# plaits_v50.net
KiCad netlist of a schematic drawn in EAGLE
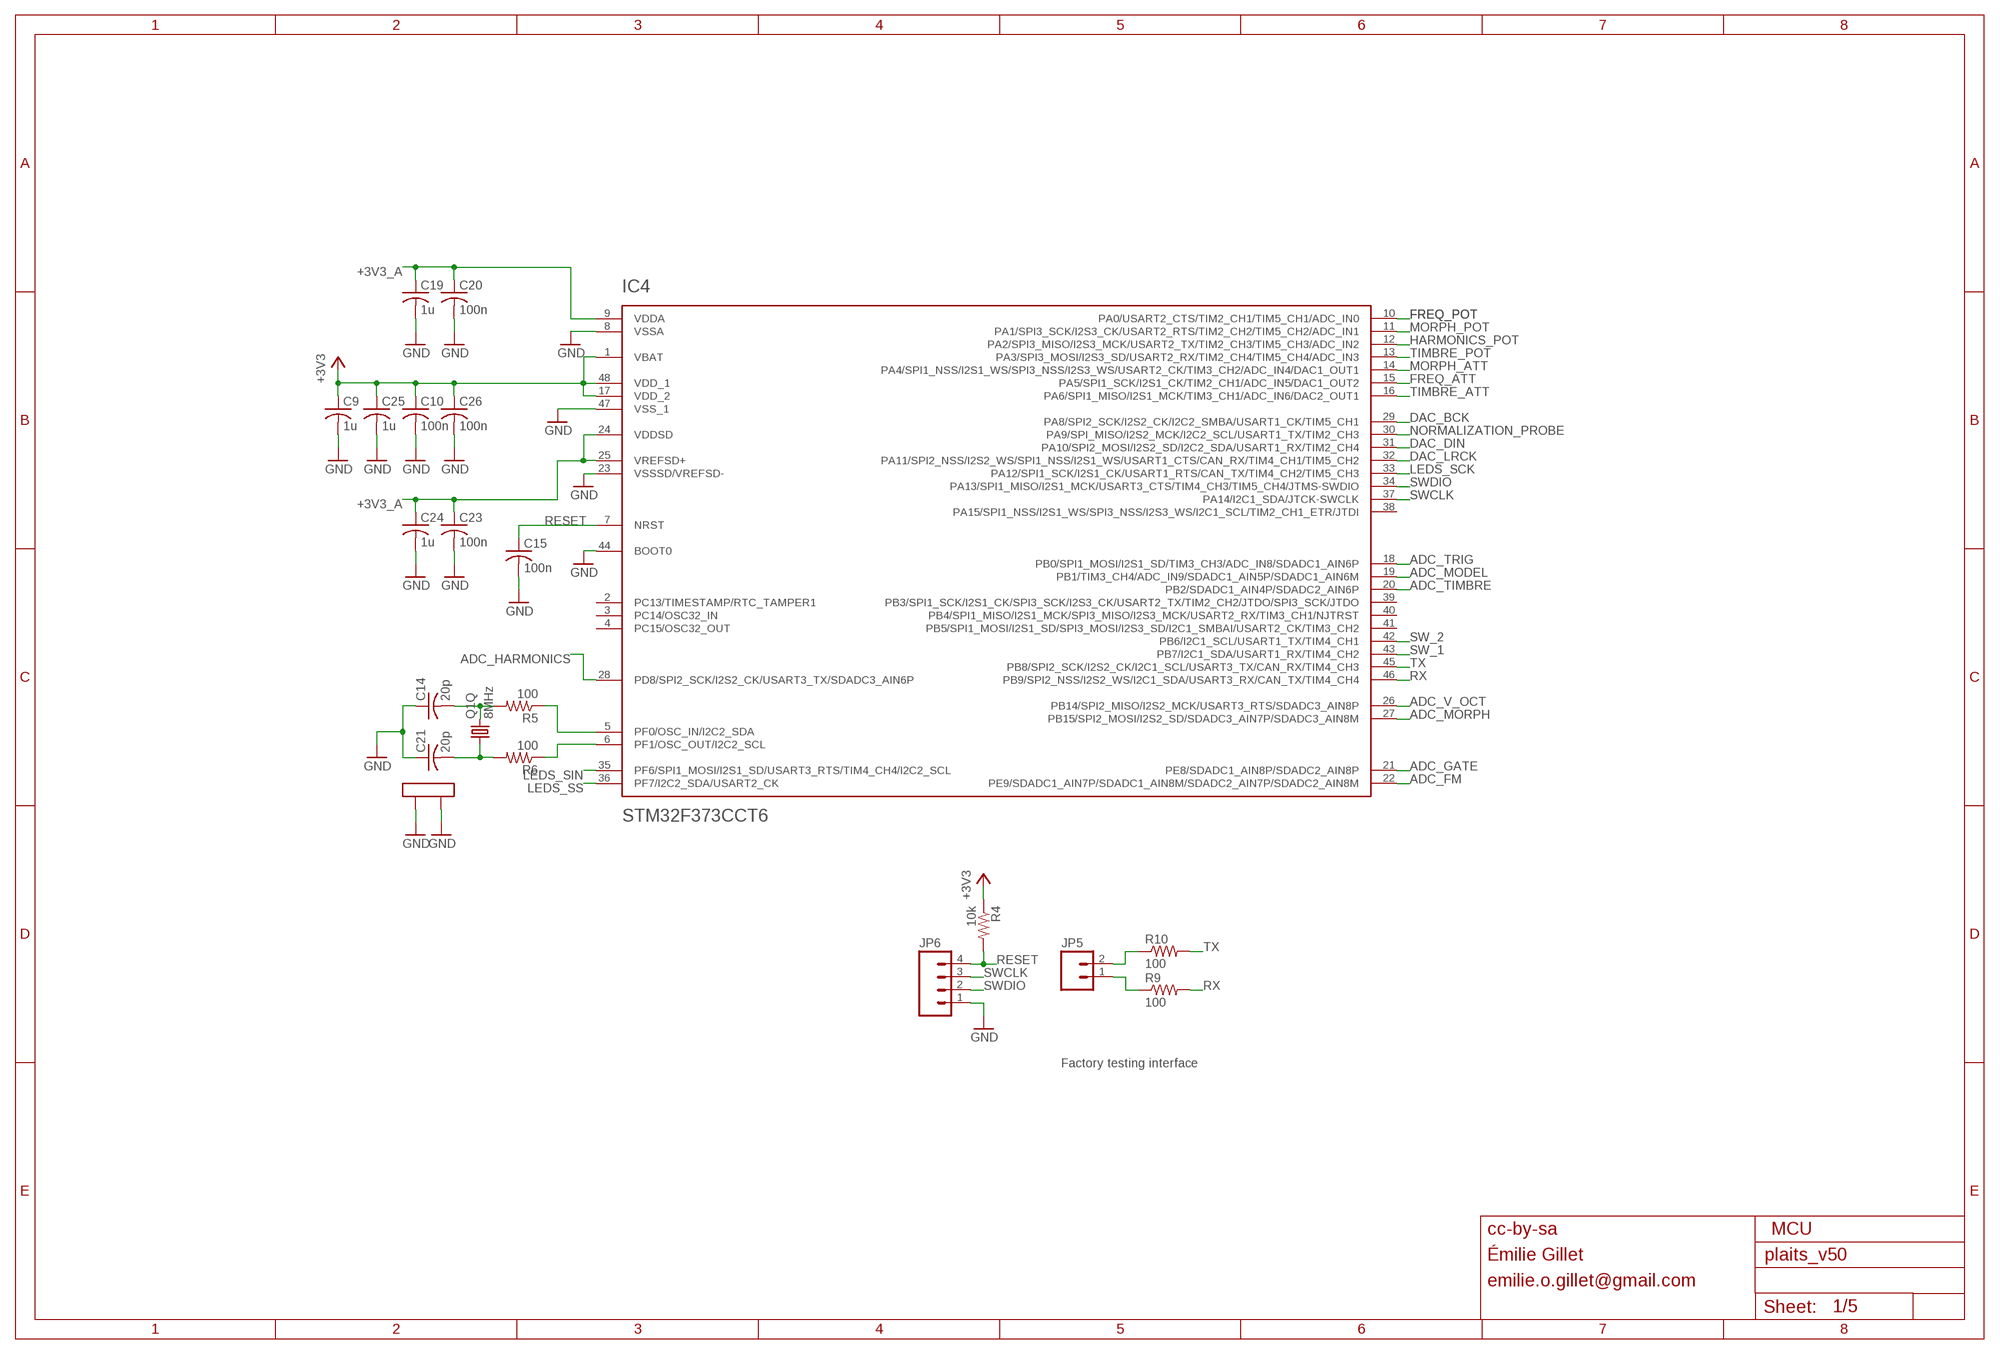
[diagram p0: schematic, sheet 1]
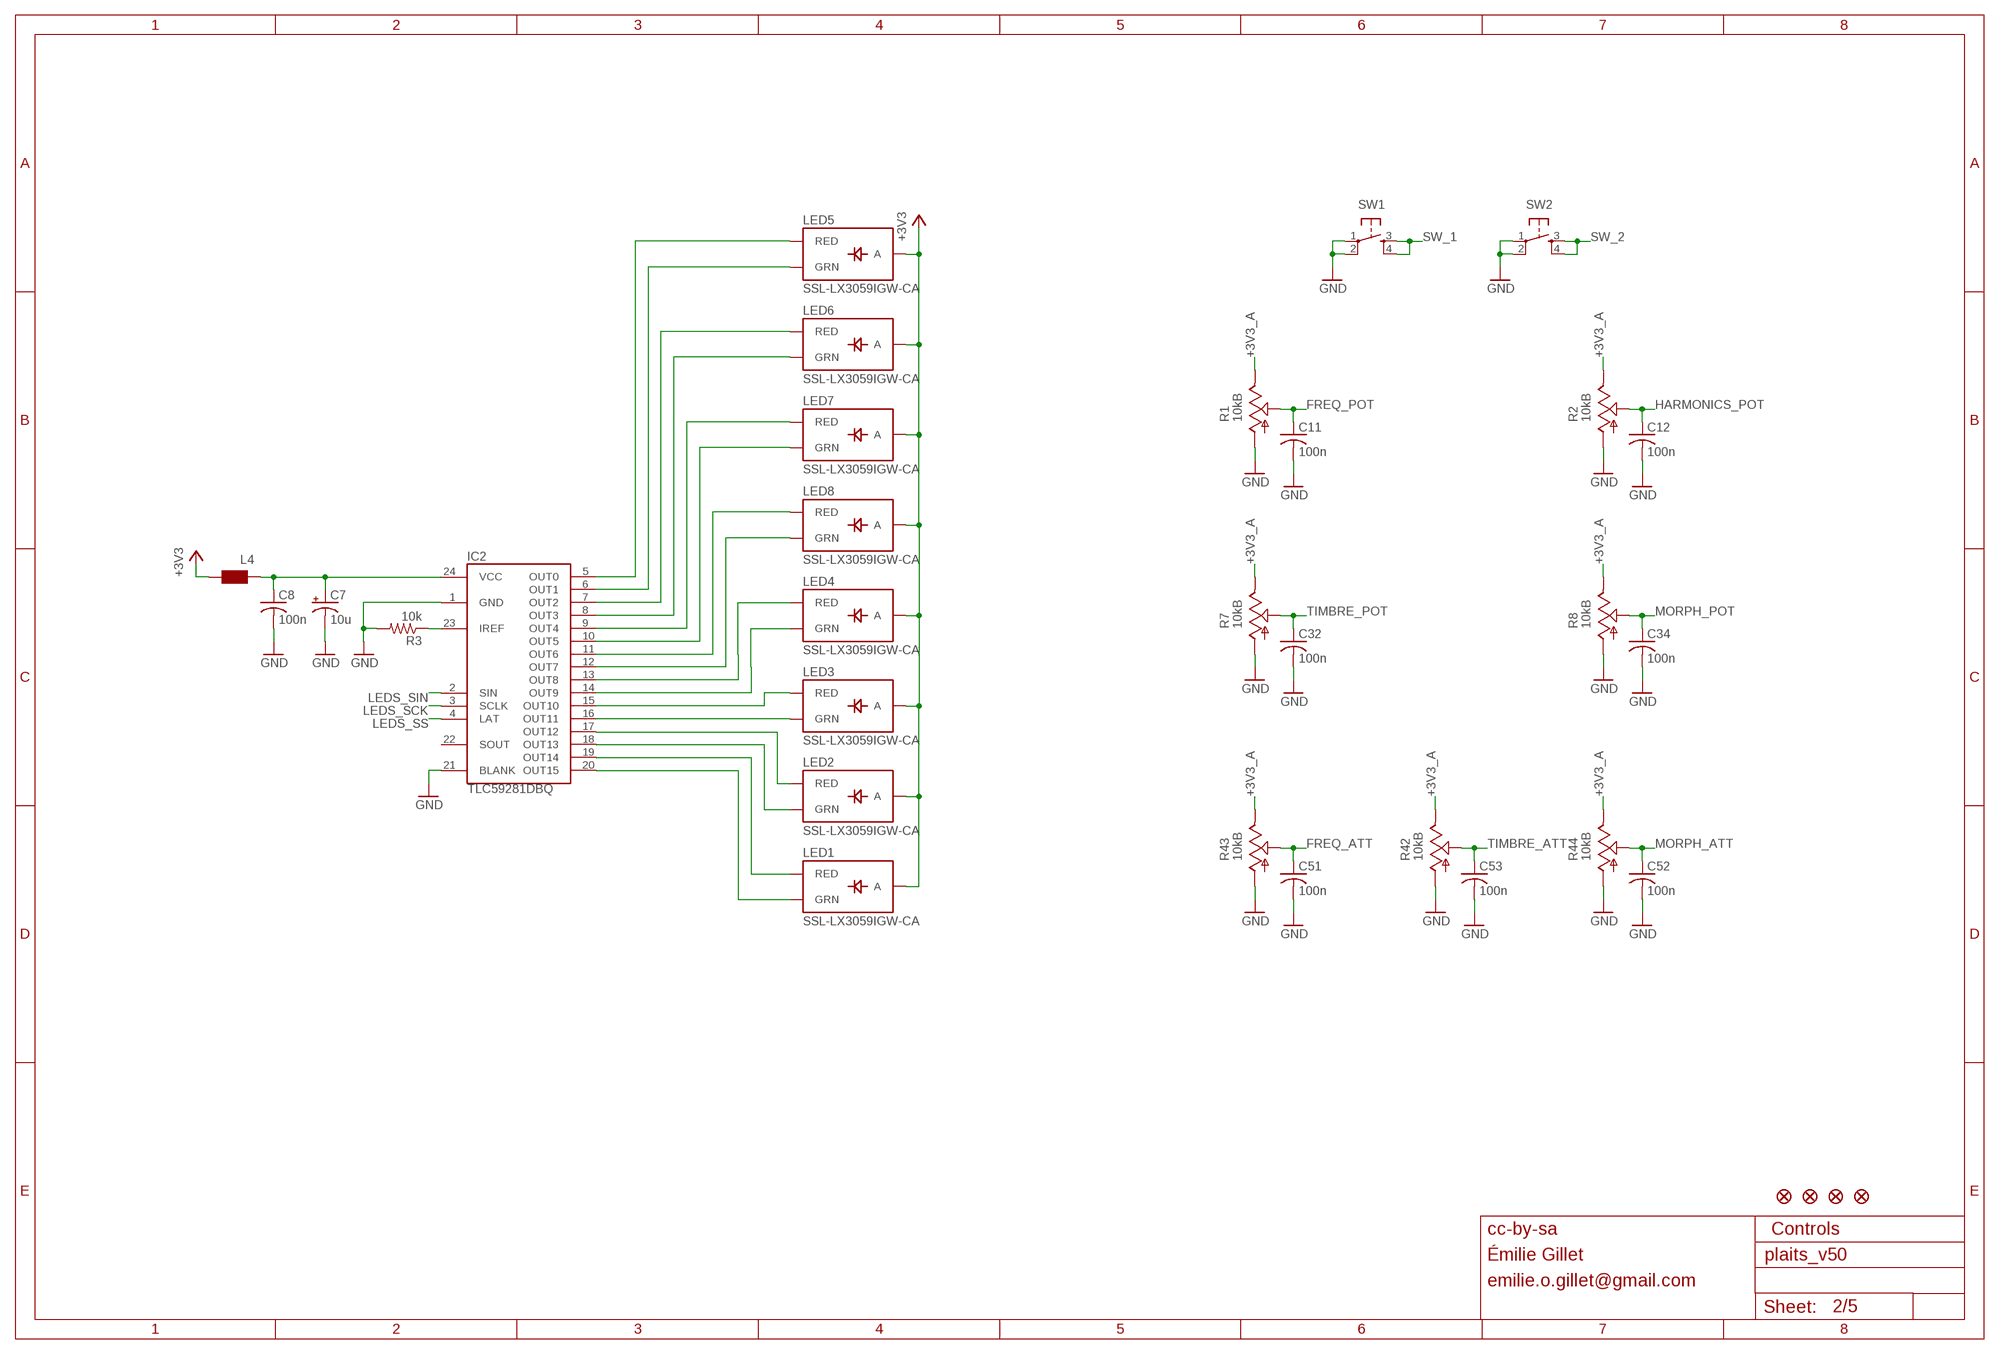
[diagram p1: schematic, sheet 2]
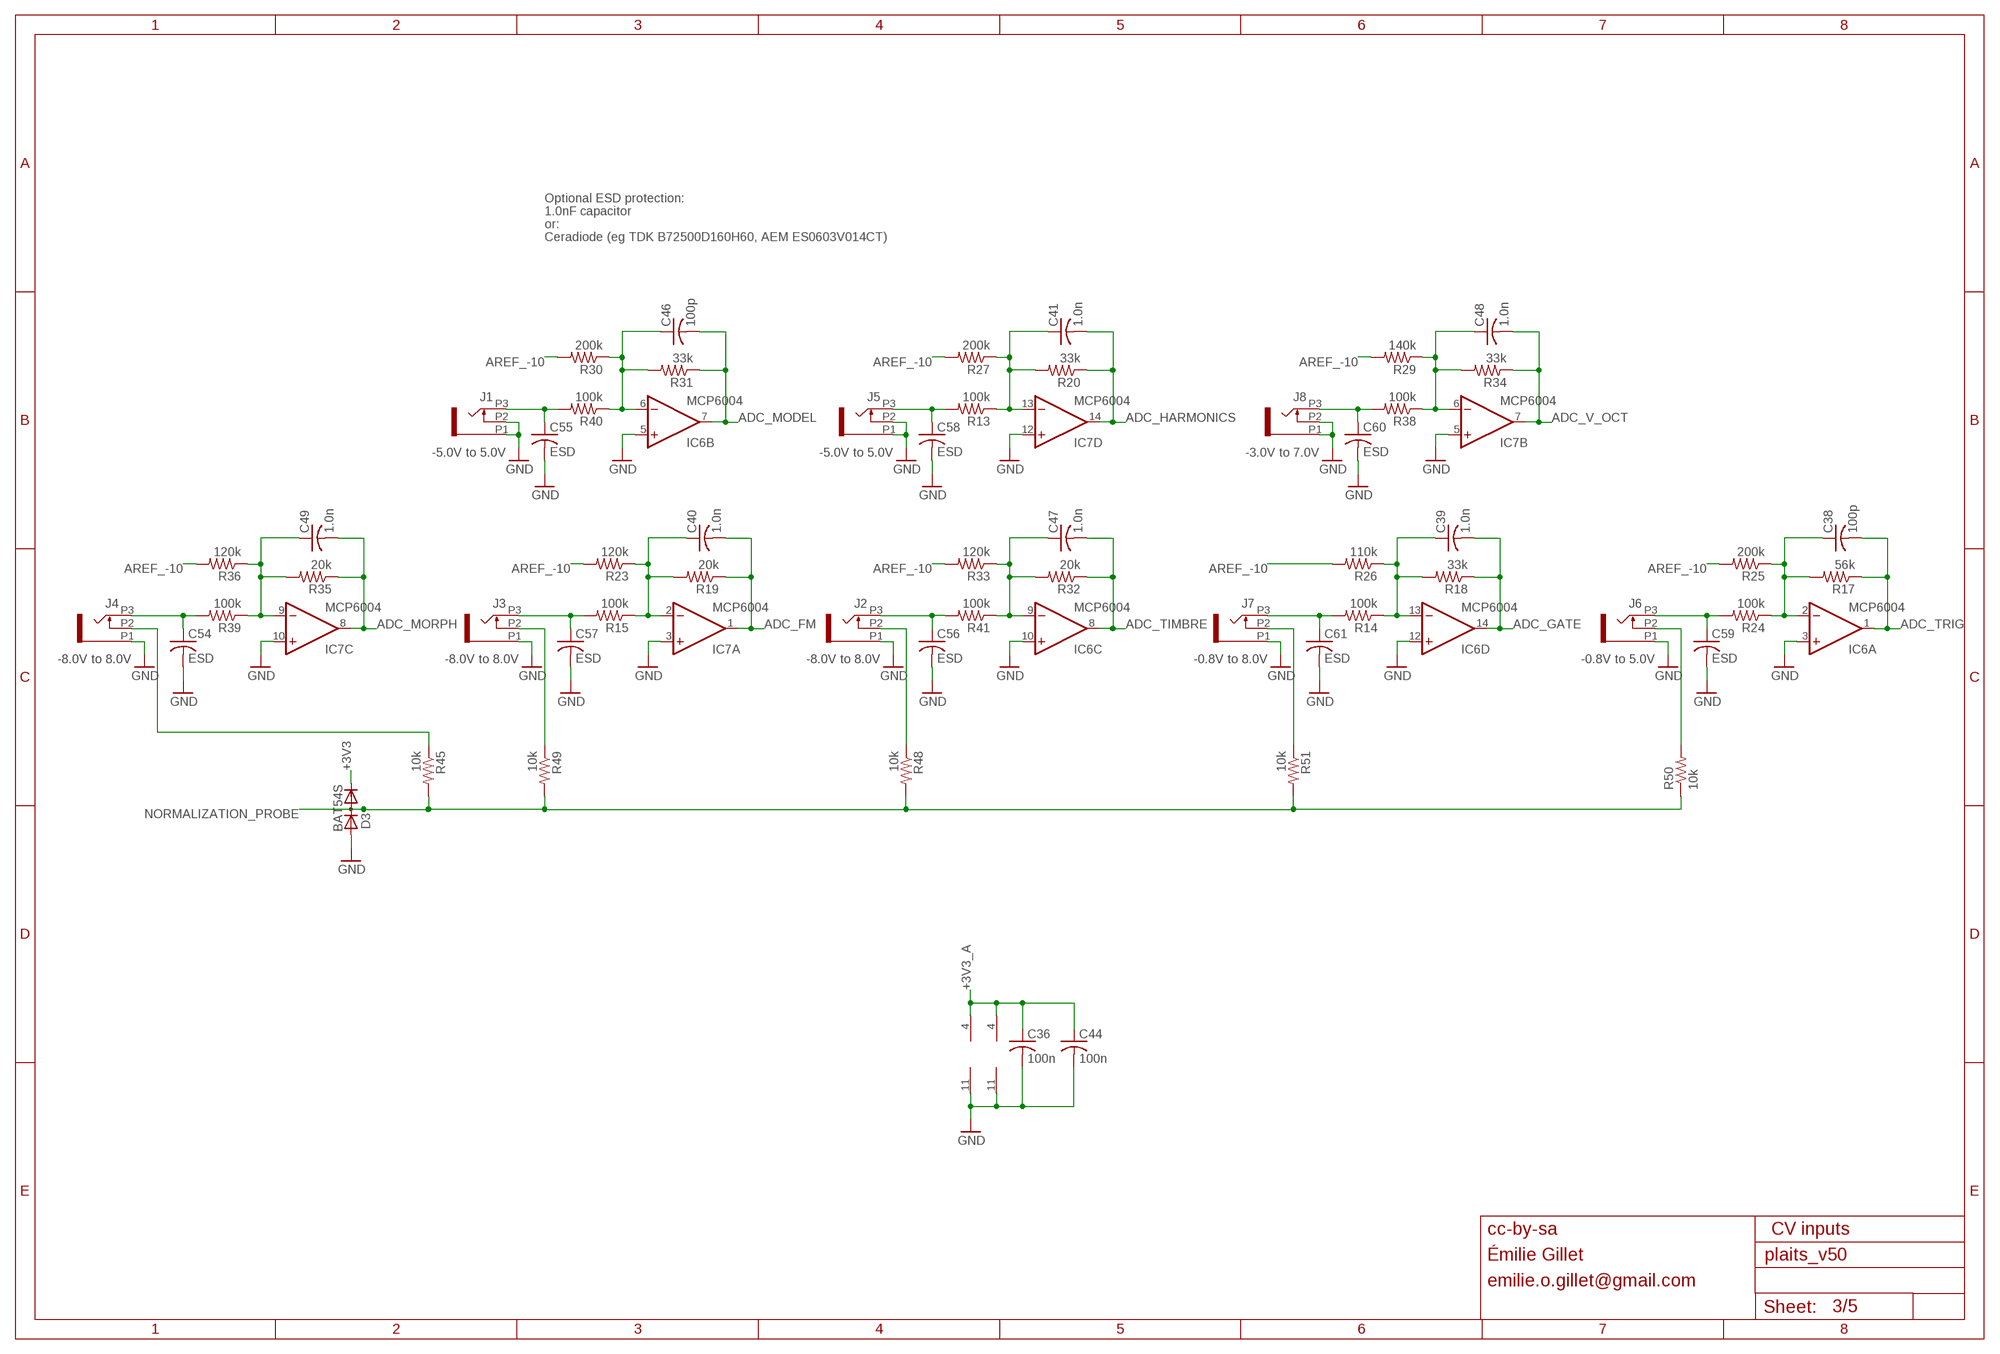
[diagram p2: schematic, sheet 3]
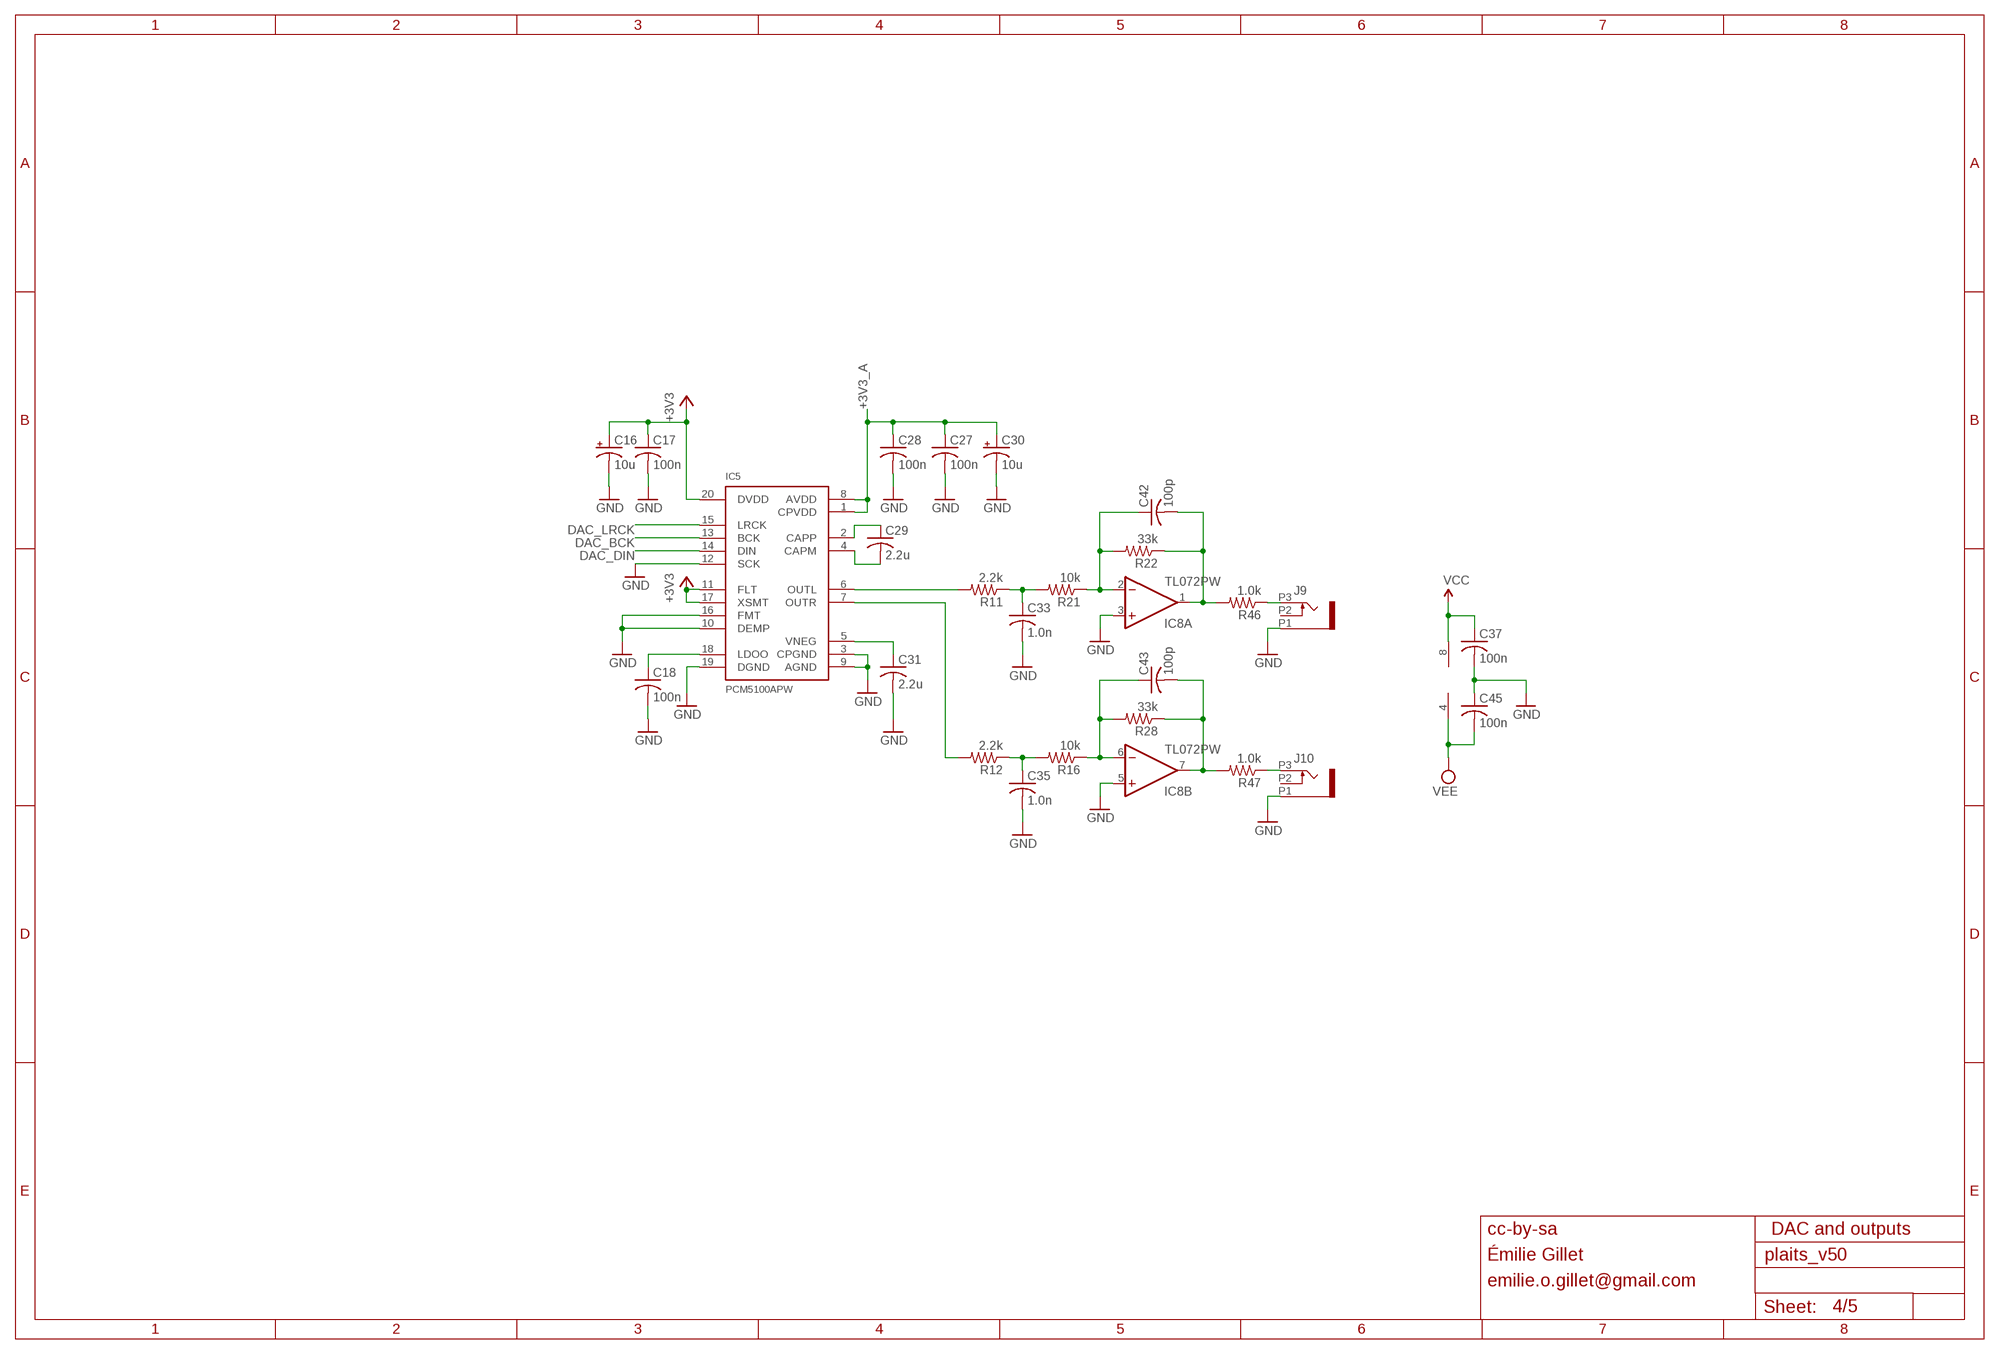
[diagram p3: schematic, sheet 4]
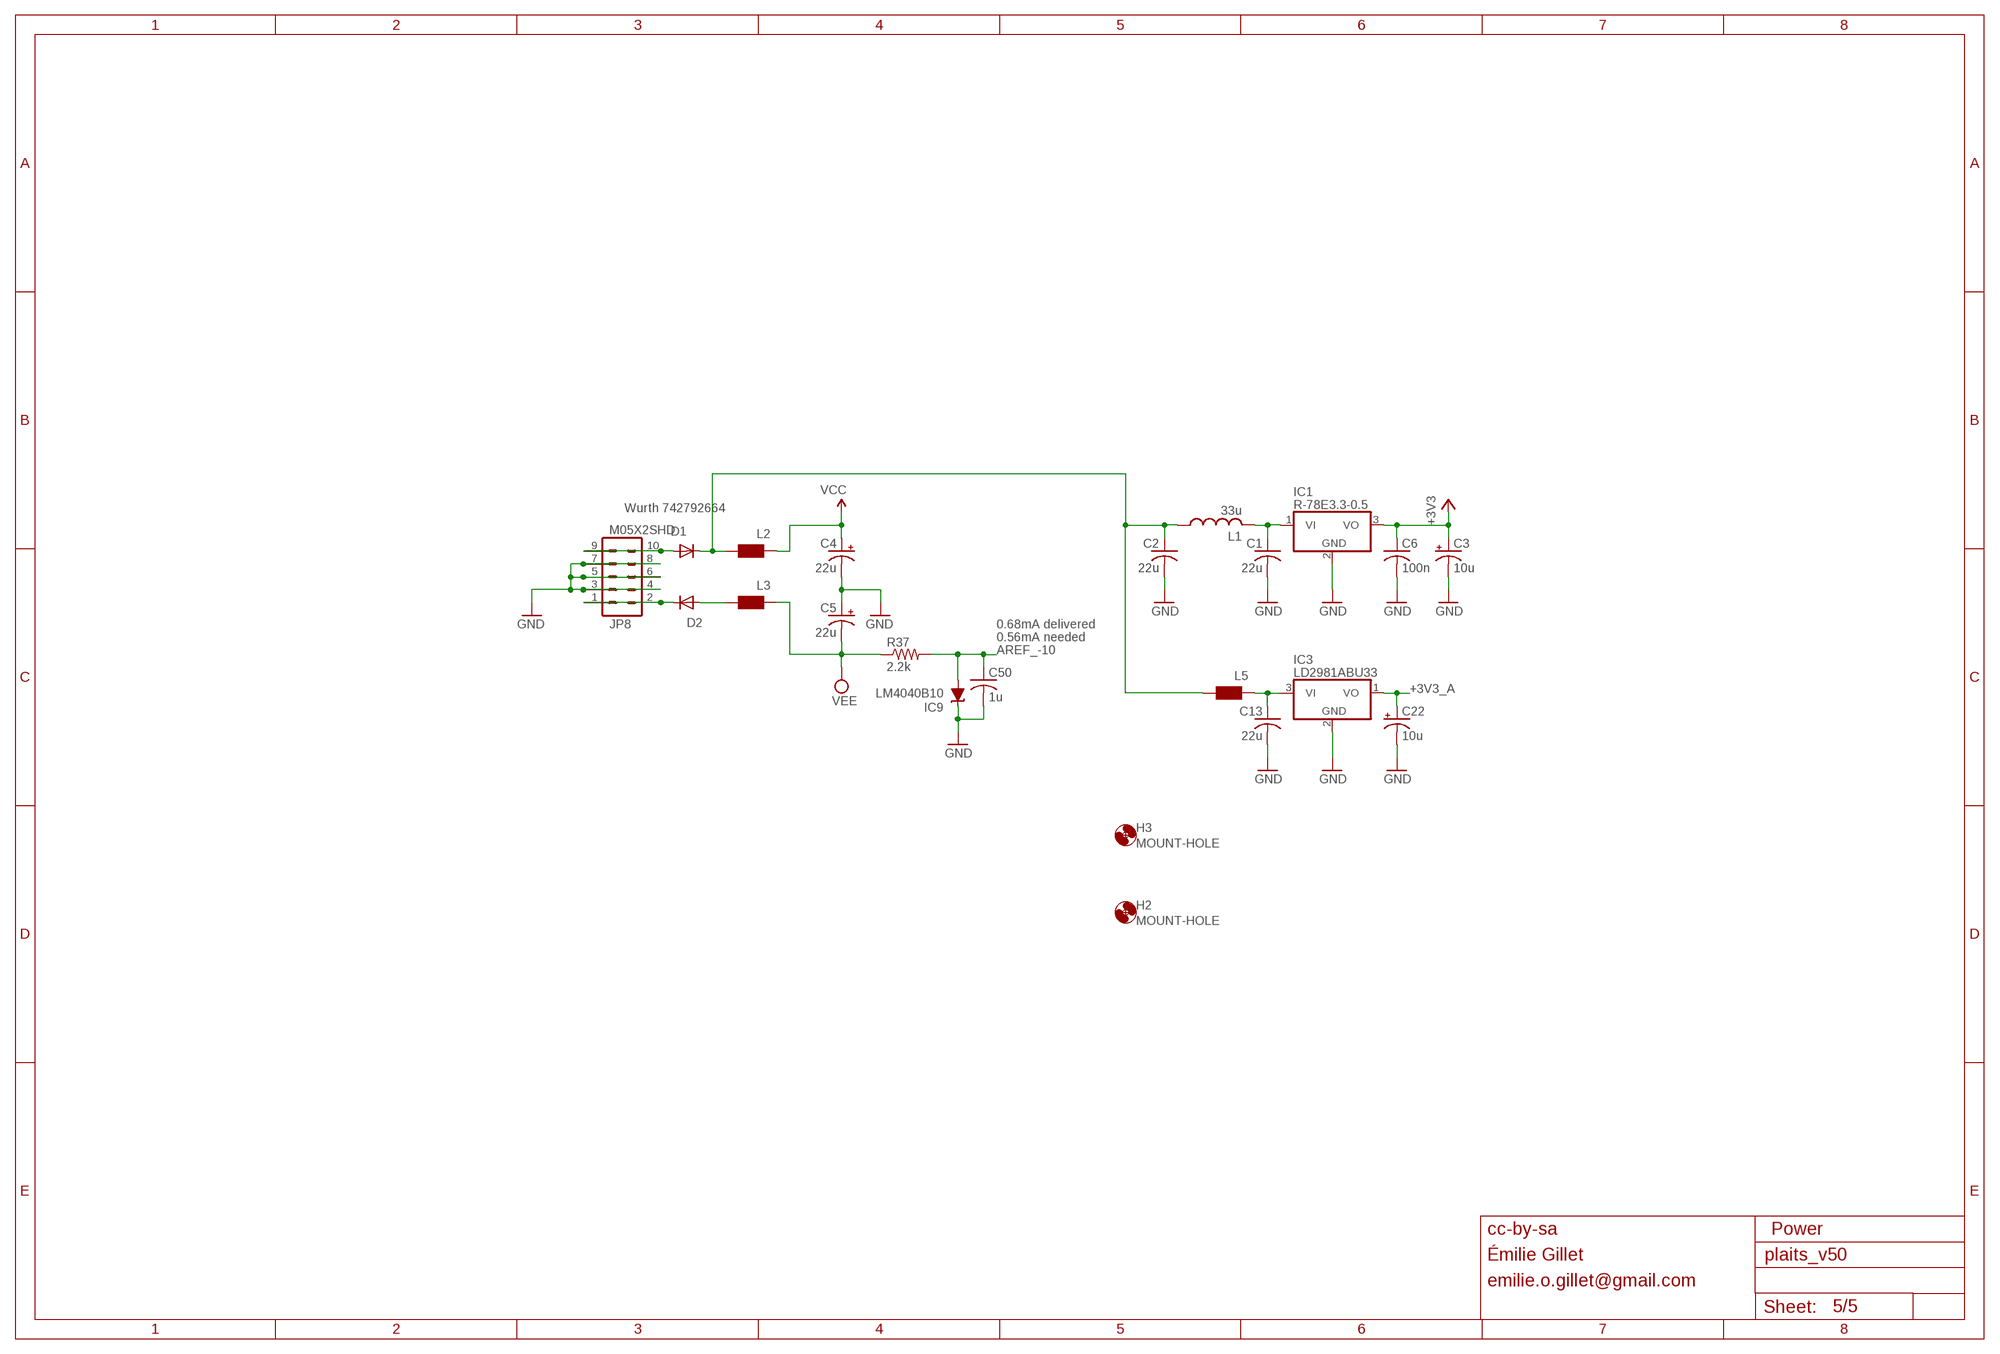
[diagram p4: schematic, sheet 5]

(export (version "E")
  (design (tool "Eeschema 10.0.6"))
  (components
    (comp (ref "C9")
      (value "1u")
      (footprint "eagle-import:C0603")
      (libsource (lib "eagle-import") (part "C-USC0603"))
    )
    (comp (ref "C10")
      (value "100n")
      (footprint "eagle-import:C0603")
      (libsource (lib "eagle-import") (part "C-USC0603"))
    )
    (comp (ref "C14")
      (value "20p")
      (footprint "eagle-import:C0603")
      (libsource (lib "eagle-import") (part "C-USC0603"))
    )
    (comp (ref "C15")
      (value "100n")
      (footprint "eagle-import:C0603")
      (libsource (lib "eagle-import") (part "C-USC0603"))
    )
    (comp (ref "C19")
      (value "1u")
      (footprint "eagle-import:C0603")
      (libsource (lib "eagle-import") (part "C-USC0603"))
    )
    (comp (ref "C20")
      (value "100n")
      (footprint "eagle-import:C0603")
      (libsource (lib "eagle-import") (part "C-USC0603"))
    )
    (comp (ref "C21")
      (value "20p")
      (footprint "eagle-import:C0603")
      (libsource (lib "eagle-import") (part "C-USC0603"))
    )
    (comp (ref "C23")
      (value "100n")
      (footprint "eagle-import:C0603")
      (libsource (lib "eagle-import") (part "C-USC0603"))
    )
    (comp (ref "C24")
      (value "1u")
      (footprint "eagle-import:C0603")
      (libsource (lib "eagle-import") (part "C-USC0603"))
    )
    (comp (ref "C25")
      (value "1u")
      (footprint "eagle-import:C0603")
      (libsource (lib "eagle-import") (part "C-USC0603"))
    )
    (comp (ref "C26")
      (value "100n")
      (footprint "eagle-import:C0603")
      (libsource (lib "eagle-import") (part "C-USC0603"))
    )
    (comp (ref "IC4")
      (value "STM32F373CCT6")
      (footprint "eagle-import:LQFP48")
      (libsource (lib "eagle-import") (part "STM32F373C"))
    )
    (comp (ref "JP5")
      (value "M02PTH")
      (footprint "eagle-import:1X02")
      (libsource (lib "eagle-import") (part "M02PTH"))
    )
    (comp (ref "JP6")
      (value "M04PTH")
      (footprint "eagle-import:1X04")
      (libsource (lib "eagle-import") (part "M04PTH"))
    )
    (comp (ref "Q1")
      (value "8MHz")
      (footprint "eagle-import:CTS406")
      (libsource (lib "eagle-import") (part "CRYSTAL"))
    )
    (comp (ref "R4")
      (value "10k")
      (footprint "eagle-import:R0603")
      (libsource (lib "eagle-import") (part "R-US_R0603"))
    )
    (comp (ref "R5")
      (value "100")
      (footprint "eagle-import:R0603")
      (libsource (lib "eagle-import") (part "R-US_R0603"))
    )
    (comp (ref "R6")
      (value "100")
      (footprint "eagle-import:R0603")
      (libsource (lib "eagle-import") (part "R-US_R0603"))
    )
    (comp (ref "R9")
      (value "100")
      (footprint "eagle-import:R0603")
      (libsource (lib "eagle-import") (part "R-US_R0603"))
    )
    (comp (ref "R10")
      (value "100")
      (footprint "eagle-import:R0603")
      (libsource (lib "eagle-import") (part "R-US_R0603"))
    )
    (comp (ref "C36")
      (value "100n")
      (footprint "eagle-import:C0603")
      (libsource (lib "eagle-import") (part "C-USC0603"))
    )
    (comp (ref "C38")
      (value "100p")
      (footprint "eagle-import:C0603")
      (libsource (lib "eagle-import") (part "C-USC0603"))
    )
    (comp (ref "C39")
      (value "1.0n")
      (footprint "eagle-import:C0603")
      (libsource (lib "eagle-import") (part "C-USC0603"))
    )
    (comp (ref "C40")
      (value "1.0n")
      (footprint "eagle-import:C0603")
      (libsource (lib "eagle-import") (part "C-USC0603"))
    )
    (comp (ref "C41")
      (value "1.0n")
      (footprint "eagle-import:C0603")
      (libsource (lib "eagle-import") (part "C-USC0603"))
    )
    (comp (ref "C44")
      (value "100n")
      (footprint "eagle-import:C0603")
      (libsource (lib "eagle-import") (part "C-USC0603"))
    )
    (comp (ref "C46")
      (value "100p")
      (footprint "eagle-import:C0603")
      (libsource (lib "eagle-import") (part "C-USC0603"))
    )
    (comp (ref "C47")
      (value "1.0n")
      (footprint "eagle-import:C0603")
      (libsource (lib "eagle-import") (part "C-USC0603"))
    )
    (comp (ref "C48")
      (value "1.0n")
      (footprint "eagle-import:C0603")
      (libsource (lib "eagle-import") (part "C-USC0603"))
    )
    (comp (ref "C49")
      (value "1.0n")
      (footprint "eagle-import:C0603")
      (libsource (lib "eagle-import") (part "C-USC0603"))
    )
    (comp (ref "C54")
      (value "ESD")
      (footprint "eagle-import:C0603")
      (libsource (lib "eagle-import") (part "C-USC0603"))
    )
    (comp (ref "C55")
      (value "ESD")
      (footprint "eagle-import:C0603")
      (libsource (lib "eagle-import") (part "C-USC0603"))
    )
    (comp (ref "C56")
      (value "ESD")
      (footprint "eagle-import:C0603")
      (libsource (lib "eagle-import") (part "C-USC0603"))
    )
    (comp (ref "C57")
      (value "ESD")
      (footprint "eagle-import:C0603")
      (libsource (lib "eagle-import") (part "C-USC0603"))
    )
    (comp (ref "C58")
      (value "ESD")
      (footprint "eagle-import:C0603")
      (libsource (lib "eagle-import") (part "C-USC0603"))
    )
    (comp (ref "C59")
      (value "ESD")
      (footprint "eagle-import:C0603")
      (libsource (lib "eagle-import") (part "C-USC0603"))
    )
    (comp (ref "C60")
      (value "ESD")
      (footprint "eagle-import:C0603")
      (libsource (lib "eagle-import") (part "C-USC0603"))
    )
    (comp (ref "C61")
      (value "ESD")
      (footprint "eagle-import:C0603")
      (libsource (lib "eagle-import") (part "C-USC0603"))
    )
    (comp (ref "D3")
      (value "BAT54S")
      (footprint "eagle-import:SOT23")
      (libsource (lib "eagle-import") (part "DIODE_2CACA-SOT23"))
    )
    (comp (ref "IC6")
      (value "MCP6004")
      (footprint "eagle-import:TSSOP14_065")
      (libsource (lib "eagle-import") (part "TL074PW"))
    )
    (comp (ref "IC7")
      (value "MCP6004")
      (footprint "eagle-import:TSSOP14_065")
      (libsource (lib "eagle-import") (part "TL074PW"))
    )
    (comp (ref "J1")
      (value "PJ301_THONKICONN6")
      (footprint "eagle-import:WQP_PJ_301M6")
      (libsource (lib "eagle-import") (part "PJ301_THONKICONN6"))
    )
    (comp (ref "J2")
      (value "PJ301_THONKICONN6")
      (footprint "eagle-import:WQP_PJ_301M6")
      (libsource (lib "eagle-import") (part "PJ301_THONKICONN6"))
    )
    (comp (ref "J3")
      (value "PJ301_THONKICONN6")
      (footprint "eagle-import:WQP_PJ_301M6")
      (libsource (lib "eagle-import") (part "PJ301_THONKICONN6"))
    )
    (comp (ref "J4")
      (value "PJ301_THONKICONN6")
      (footprint "eagle-import:WQP_PJ_301M6")
      (libsource (lib "eagle-import") (part "PJ301_THONKICONN6"))
    )
    (comp (ref "J5")
      (value "PJ301_THONKICONN6")
      (footprint "eagle-import:WQP_PJ_301M6")
      (libsource (lib "eagle-import") (part "PJ301_THONKICONN6"))
    )
    (comp (ref "J6")
      (value "PJ301_THONKICONN6")
      (footprint "eagle-import:WQP_PJ_301M6")
      (libsource (lib "eagle-import") (part "PJ301_THONKICONN6"))
    )
    (comp (ref "J7")
      (value "PJ301_THONKICONN6")
      (footprint "eagle-import:WQP_PJ_301M6")
      (libsource (lib "eagle-import") (part "PJ301_THONKICONN6"))
    )
    (comp (ref "J8")
      (value "PJ301_THONKICONN6")
      (footprint "eagle-import:WQP_PJ_301M6")
      (libsource (lib "eagle-import") (part "PJ301_THONKICONN6"))
    )
    (comp (ref "R13")
      (value "100k")
      (footprint "eagle-import:R0603")
      (libsource (lib "eagle-import") (part "R-US_R0603"))
    )
    (comp (ref "R14")
      (value "100k")
      (footprint "eagle-import:R0603")
      (libsource (lib "eagle-import") (part "R-US_R0603"))
    )
    (comp (ref "R15")
      (value "100k")
      (footprint "eagle-import:R0603")
      (libsource (lib "eagle-import") (part "R-US_R0603"))
    )
    (comp (ref "R17")
      (value "56k")
      (footprint "eagle-import:R0603")
      (libsource (lib "eagle-import") (part "R-US_R0603"))
    )
    (comp (ref "R18")
      (value "33k")
      (footprint "eagle-import:R0603")
      (libsource (lib "eagle-import") (part "R-US_R0603"))
    )
    (comp (ref "R19")
      (value "20k")
      (footprint "eagle-import:R0603")
      (libsource (lib "eagle-import") (part "R-US_R0603"))
    )
    (comp (ref "R20")
      (value "33k")
      (footprint "eagle-import:R0603")
      (libsource (lib "eagle-import") (part "R-US_R0603"))
    )
    (comp (ref "R23")
      (value "120k")
      (footprint "eagle-import:R0603")
      (libsource (lib "eagle-import") (part "R-US_R0603"))
    )
    (comp (ref "R24")
      (value "100k")
      (footprint "eagle-import:R0603")
      (libsource (lib "eagle-import") (part "R-US_R0603"))
    )
    (comp (ref "R25")
      (value "200k")
      (footprint "eagle-import:R0603")
      (libsource (lib "eagle-import") (part "R-US_R0603"))
    )
    (comp (ref "R26")
      (value "110k")
      (footprint "eagle-import:R0603")
      (libsource (lib "eagle-import") (part "R-US_R0603"))
    )
    (comp (ref "R27")
      (value "200k")
      (footprint "eagle-import:R0603")
      (libsource (lib "eagle-import") (part "R-US_R0603"))
    )
    (comp (ref "R29")
      (value "140k")
      (footprint "eagle-import:R0603")
      (libsource (lib "eagle-import") (part "R-US_R0603"))
    )
    (comp (ref "R30")
      (value "200k")
      (footprint "eagle-import:R0603")
      (libsource (lib "eagle-import") (part "R-US_R0603"))
    )
    (comp (ref "R31")
      (value "33k")
      (footprint "eagle-import:R0603")
      (libsource (lib "eagle-import") (part "R-US_R0603"))
    )
    (comp (ref "R32")
      (value "20k")
      (footprint "eagle-import:R0603")
      (libsource (lib "eagle-import") (part "R-US_R0603"))
    )
    (comp (ref "R33")
      (value "120k")
      (footprint "eagle-import:R0603")
      (libsource (lib "eagle-import") (part "R-US_R0603"))
    )
    (comp (ref "R34")
      (value "33k")
      (footprint "eagle-import:R0603")
      (libsource (lib "eagle-import") (part "R-US_R0603"))
    )
    (comp (ref "R35")
      (value "20k")
      (footprint "eagle-import:R0603")
      (libsource (lib "eagle-import") (part "R-US_R0603"))
    )
    (comp (ref "R36")
      (value "120k")
      (footprint "eagle-import:R0603")
      (libsource (lib "eagle-import") (part "R-US_R0603"))
    )
    (comp (ref "R38")
      (value "100k")
      (footprint "eagle-import:R0603")
      (libsource (lib "eagle-import") (part "R-US_R0603"))
    )
    (comp (ref "R39")
      (value "100k")
      (footprint "eagle-import:R0603")
      (libsource (lib "eagle-import") (part "R-US_R0603"))
    )
    (comp (ref "R40")
      (value "100k")
      (footprint "eagle-import:R0603")
      (libsource (lib "eagle-import") (part "R-US_R0603"))
    )
    (comp (ref "R41")
      (value "100k")
      (footprint "eagle-import:R0603")
      (libsource (lib "eagle-import") (part "R-US_R0603"))
    )
    (comp (ref "R45")
      (value "10k")
      (footprint "eagle-import:R0603")
      (libsource (lib "eagle-import") (part "R-US_R0603"))
    )
    (comp (ref "R48")
      (value "10k")
      (footprint "eagle-import:R0603")
      (libsource (lib "eagle-import") (part "R-US_R0603"))
    )
    (comp (ref "R49")
      (value "10k")
      (footprint "eagle-import:R0603")
      (libsource (lib "eagle-import") (part "R-US_R0603"))
    )
    (comp (ref "R50")
      (value "10k")
      (footprint "eagle-import:R0603")
      (libsource (lib "eagle-import") (part "R-US_R0603"))
    )
    (comp (ref "R51")
      (value "10k")
      (footprint "eagle-import:R0603")
      (libsource (lib "eagle-import") (part "R-US_R0603"))
    )
    (comp (ref "C7")
      (value "10u")
      (footprint "eagle-import:PANASONIC_A")
      (libsource (lib "eagle-import") (part "CPOL-USA"))
    )
    (comp (ref "C8")
      (value "100n")
      (footprint "eagle-import:C0603")
      (libsource (lib "eagle-import") (part "C-USC0603"))
    )
    (comp (ref "C11")
      (value "100n")
      (footprint "eagle-import:C0603")
      (libsource (lib "eagle-import") (part "C-USC0603"))
    )
    (comp (ref "C12")
      (value "100n")
      (footprint "eagle-import:C0603")
      (libsource (lib "eagle-import") (part "C-USC0603"))
    )
    (comp (ref "C32")
      (value "100n")
      (footprint "eagle-import:C0603")
      (libsource (lib "eagle-import") (part "C-USC0603"))
    )
    (comp (ref "C34")
      (value "100n")
      (footprint "eagle-import:C0603")
      (libsource (lib "eagle-import") (part "C-USC0603"))
    )
    (comp (ref "C51")
      (value "100n")
      (footprint "eagle-import:C0603")
      (libsource (lib "eagle-import") (part "C-USC0603"))
    )
    (comp (ref "C52")
      (value "100n")
      (footprint "eagle-import:C0603")
      (libsource (lib "eagle-import") (part "C-USC0603"))
    )
    (comp (ref "C53")
      (value "100n")
      (footprint "eagle-import:C0603")
      (libsource (lib "eagle-import") (part "C-USC0603"))
    )
    (comp (ref "IC2")
      (value "TLC59281DBQ")
      (footprint "eagle-import:TSSOP24_0635")
      (libsource (lib "eagle-import") (part "TLC59281DBQ"))
    )
    (comp (ref "JP1")
      (value "FIDUCIAL1X2")
      (footprint "eagle-import:FIDUCIAL-1X2")
      (libsource (lib "eagle-import") (part "FIDUCIAL1X2"))
    )
    (comp (ref "JP2")
      (value "FIDUCIAL1X2")
      (footprint "eagle-import:FIDUCIAL-1X2")
      (libsource (lib "eagle-import") (part "FIDUCIAL1X2"))
    )
    (comp (ref "JP3")
      (value "FIDUCIAL1X2")
      (footprint "eagle-import:FIDUCIAL-1X2")
      (libsource (lib "eagle-import") (part "FIDUCIAL1X2"))
    )
    (comp (ref "JP4")
      (value "FIDUCIAL1X2")
      (footprint "eagle-import:FIDUCIAL-1X2")
      (libsource (lib "eagle-import") (part "FIDUCIAL1X2"))
    )
    (comp (ref "L4")
      (value "WE-CBF_0603")
      (footprint "eagle-import:0603")
      (libsource (lib "eagle-import") (part "WE-CBF_0603"))
    )
    (comp (ref "LED1")
      (value "SSL-LX3059IGW-CA")
      (footprint "eagle-import:LED-BICOLOR-THROUGHHOLE-LUMEX")
      (libsource (lib "eagle-import") (part "LED-BICOLOR-THROUGHHOLE-CA"))
    )
    (comp (ref "LED2")
      (value "SSL-LX3059IGW-CA")
      (footprint "eagle-import:LED-BICOLOR-THROUGHHOLE-LUMEX")
      (libsource (lib "eagle-import") (part "LED-BICOLOR-THROUGHHOLE-CA"))
    )
    (comp (ref "LED3")
      (value "SSL-LX3059IGW-CA")
      (footprint "eagle-import:LED-BICOLOR-THROUGHHOLE-LUMEX")
      (libsource (lib "eagle-import") (part "LED-BICOLOR-THROUGHHOLE-CA"))
    )
    (comp (ref "LED4")
      (value "SSL-LX3059IGW-CA")
      (footprint "eagle-import:LED-BICOLOR-THROUGHHOLE-LUMEX")
      (libsource (lib "eagle-import") (part "LED-BICOLOR-THROUGHHOLE-CA"))
    )
    (comp (ref "LED5")
      (value "SSL-LX3059IGW-CA")
      (footprint "eagle-import:LED-BICOLOR-THROUGHHOLE-LUMEX")
      (libsource (lib "eagle-import") (part "LED-BICOLOR-THROUGHHOLE-CA"))
    )
    (comp (ref "LED6")
      (value "SSL-LX3059IGW-CA")
      (footprint "eagle-import:LED-BICOLOR-THROUGHHOLE-LUMEX")
      (libsource (lib "eagle-import") (part "LED-BICOLOR-THROUGHHOLE-CA"))
    )
    (comp (ref "LED7")
      (value "SSL-LX3059IGW-CA")
      (footprint "eagle-import:LED-BICOLOR-THROUGHHOLE-LUMEX")
      (libsource (lib "eagle-import") (part "LED-BICOLOR-THROUGHHOLE-CA"))
    )
    (comp (ref "LED8")
      (value "SSL-LX3059IGW-CA")
      (footprint "eagle-import:LED-BICOLOR-THROUGHHOLE-LUMEX")
      (libsource (lib "eagle-import") (part "LED-BICOLOR-THROUGHHOLE-CA"))
    )
    (comp (ref "R1")
      (value "10kB")
      (footprint "eagle-import:ALPS_POT_VERTICAL_PS")
      (libsource (lib "eagle-import") (part "POT_USVERTICAL_PS"))
    )
    (comp (ref "R2")
      (value "10kB")
      (footprint "eagle-import:ALPS_POT_VERTICAL_PS")
      (libsource (lib "eagle-import") (part "POT_USVERTICAL_PS"))
    )
    (comp (ref "R3")
      (value "10k")
      (footprint "eagle-import:R0603")
      (libsource (lib "eagle-import") (part "R-US_R0603"))
    )
    (comp (ref "R7")
      (value "10kB")
      (footprint "eagle-import:ALPS_POT_VERTICAL_PS")
      (libsource (lib "eagle-import") (part "POT_USVERTICAL_PS"))
    )
    (comp (ref "R8")
      (value "10kB")
      (footprint "eagle-import:ALPS_POT_VERTICAL_PS")
      (libsource (lib "eagle-import") (part "POT_USVERTICAL_PS"))
    )
    (comp (ref "R42")
      (value "10kB")
      (footprint "eagle-import:ALPS_POT_VERTICAL")
      (libsource (lib "eagle-import") (part "POT_USVERTICAL"))
    )
    (comp (ref "R43")
      (value "10kB")
      (footprint "eagle-import:ALPS_POT_VERTICAL")
      (libsource (lib "eagle-import") (part "POT_USVERTICAL"))
    )
    (comp (ref "R44")
      (value "10kB")
      (footprint "eagle-import:ALPS_POT_VERTICAL")
      (libsource (lib "eagle-import") (part "POT_USVERTICAL"))
    )
    (comp (ref "SW1")
      (value "TAC_SWITCHPTH")
      (footprint "eagle-import:TACTILE-PTH")
      (libsource (lib "eagle-import") (part "TAC_SWITCHPTH"))
    )
    (comp (ref "SW2")
      (value "TAC_SWITCHPTH")
      (footprint "eagle-import:TACTILE-PTH")
      (libsource (lib "eagle-import") (part "TAC_SWITCHPTH"))
    )
    (comp (ref "C16")
      (value "10u")
      (footprint "eagle-import:PANASONIC_A")
      (libsource (lib "eagle-import") (part "CPOL-USA"))
    )
    (comp (ref "C17")
      (value "100n")
      (footprint "eagle-import:C0603")
      (libsource (lib "eagle-import") (part "C-USC0603"))
    )
    (comp (ref "C18")
      (value "100n")
      (footprint "eagle-import:C0603")
      (libsource (lib "eagle-import") (part "C-USC0603"))
    )
    (comp (ref "C27")
      (value "100n")
      (footprint "eagle-import:C0603")
      (libsource (lib "eagle-import") (part "C-USC0603"))
    )
    (comp (ref "C28")
      (value "100n")
      (footprint "eagle-import:C0603")
      (libsource (lib "eagle-import") (part "C-USC0603"))
    )
    (comp (ref "C29")
      (value "2.2u")
      (footprint "eagle-import:C0805")
      (libsource (lib "eagle-import") (part "C-USC0805"))
    )
    (comp (ref "C30")
      (value "10u")
      (footprint "eagle-import:PANASONIC_A")
      (libsource (lib "eagle-import") (part "CPOL-USA"))
    )
    (comp (ref "C31")
      (value "2.2u")
      (footprint "eagle-import:C0805")
      (libsource (lib "eagle-import") (part "C-USC0805"))
    )
    (comp (ref "C33")
      (value "1.0n")
      (footprint "eagle-import:C0603")
      (libsource (lib "eagle-import") (part "C-USC0603"))
    )
    (comp (ref "C35")
      (value "1.0n")
      (footprint "eagle-import:C0603")
      (libsource (lib "eagle-import") (part "C-USC0603"))
    )
    (comp (ref "C37")
      (value "100n")
      (footprint "eagle-import:C0603")
      (libsource (lib "eagle-import") (part "C-USC0603"))
    )
    (comp (ref "C42")
      (value "100p")
      (footprint "eagle-import:C0603")
      (libsource (lib "eagle-import") (part "C-USC0603"))
    )
    (comp (ref "C43")
      (value "100p")
      (footprint "eagle-import:C0603")
      (libsource (lib "eagle-import") (part "C-USC0603"))
    )
    (comp (ref "C45")
      (value "100n")
      (footprint "eagle-import:C0603")
      (libsource (lib "eagle-import") (part "C-USC0603"))
    )
    (comp (ref "IC5")
      (value "PCM5100APW")
      (footprint "eagle-import:SSOP20")
      (libsource (lib "eagle-import") (part "PCM5100PW"))
    )
    (comp (ref "IC8")
      (value "TL072PW")
      (footprint "eagle-import:TSSOP08")
      (libsource (lib "eagle-import") (part "TL072PW"))
    )
    (comp (ref "J9")
      (value "PJ301_THONKICONN6")
      (footprint "eagle-import:WQP_PJ_301M6")
      (libsource (lib "eagle-import") (part "PJ301_THONKICONN6"))
    )
    (comp (ref "J10")
      (value "PJ301_THONKICONN6")
      (footprint "eagle-import:WQP_PJ_301M6")
      (libsource (lib "eagle-import") (part "PJ301_THONKICONN6"))
    )
    (comp (ref "R11")
      (value "2.2k")
      (footprint "eagle-import:R0603")
      (libsource (lib "eagle-import") (part "R-US_R0603"))
    )
    (comp (ref "R12")
      (value "2.2k")
      (footprint "eagle-import:R0603")
      (libsource (lib "eagle-import") (part "R-US_R0603"))
    )
    (comp (ref "R16")
      (value "10k")
      (footprint "eagle-import:R0603")
      (libsource (lib "eagle-import") (part "R-US_R0603"))
    )
    (comp (ref "R21")
      (value "10k")
      (footprint "eagle-import:R0603")
      (libsource (lib "eagle-import") (part "R-US_R0603"))
    )
    (comp (ref "R22")
      (value "33k")
      (footprint "eagle-import:R0603")
      (libsource (lib "eagle-import") (part "R-US_R0603"))
    )
    (comp (ref "R28")
      (value "33k")
      (footprint "eagle-import:R0603")
      (libsource (lib "eagle-import") (part "R-US_R0603"))
    )
    (comp (ref "R46")
      (value "1.0k")
      (footprint "eagle-import:R0603")
      (libsource (lib "eagle-import") (part "R-US_R0603"))
    )
    (comp (ref "R47")
      (value "1.0k")
      (footprint "eagle-import:R0603")
      (libsource (lib "eagle-import") (part "R-US_R0603"))
    )
    (comp (ref "C1")
      (value "22u")
      (footprint "eagle-import:C1206")
      (libsource (lib "eagle-import") (part "C-USC1206"))
    )
    (comp (ref "C2")
      (value "22u")
      (footprint "eagle-import:C1206")
      (libsource (lib "eagle-import") (part "C-USC1206"))
    )
    (comp (ref "C3")
      (value "10u")
      (footprint "eagle-import:PANASONIC_A")
      (libsource (lib "eagle-import") (part "CPOL-USA"))
    )
    (comp (ref "C4")
      (value "22u")
      (footprint "eagle-import:PANASONIC_B")
      (libsource (lib "eagle-import") (part "CPOL-USB"))
    )
    (comp (ref "C5")
      (value "22u")
      (footprint "eagle-import:PANASONIC_B")
      (libsource (lib "eagle-import") (part "CPOL-USB"))
    )
    (comp (ref "C6")
      (value "100n")
      (footprint "eagle-import:C0603")
      (libsource (lib "eagle-import") (part "C-USC0603"))
    )
    (comp (ref "C13")
      (value "22u")
      (footprint "eagle-import:C1206")
      (libsource (lib "eagle-import") (part "C-USC1206"))
    )
    (comp (ref "C22")
      (value "10u")
      (footprint "eagle-import:PANASONIC_A")
      (libsource (lib "eagle-import") (part "CPOL-USA"))
    )
    (comp (ref "C50")
      (value "1u")
      (footprint "eagle-import:C0603")
      (libsource (lib "eagle-import") (part "C-USC0603"))
    )
    (comp (ref "D1")
      (value "1N5819HW")
      (footprint "eagle-import:SOD123")
      (libsource (lib "eagle-import") (part "DIODE-SOD123"))
    )
    (comp (ref "D2")
      (value "1N5819HW")
      (footprint "eagle-import:SOD123")
      (libsource (lib "eagle-import") (part "DIODE-SOD123"))
    )
    (comp (ref "H2")
      (value "MOUNT-HOLE")
      (footprint "eagle-import:3,0TINY")
      (libsource (lib "eagle-import") (part "MOUNT-HOLE3.0TINY"))
    )
    (comp (ref "H3")
      (value "MOUNT-HOLE")
      (footprint "eagle-import:3,0TINY")
      (libsource (lib "eagle-import") (part "MOUNT-HOLE3.0TINY"))
    )
    (comp (ref "IC1")
      (value "R-78E3.3-0.5")
      (footprint "eagle-import:WE78")
      (libsource (lib "eagle-import") (part "WE173950378"))
    )
    (comp (ref "IC3")
      (value "LD2981ABU33")
      (footprint "eagle-import:SOT89")
      (libsource (lib "eagle-import") (part "LD2981ABU"))
    )
    (comp (ref "IC9")
      (value "LM4040B10")
      (footprint "eagle-import:DBZ_R-PDSO-G3")
      (libsource (lib "eagle-import") (part "LM4041DBZB12"))
    )
    (comp (ref "JP8")
      (value "M05X2SHD")
      (footprint "eagle-import:2X5-SHROUDED")
      (libsource (lib "eagle-import") (part "M05X2SHD"))
    )
    (comp (ref "L1")
      (value "33u")
      (footprint "eagle-import:L2012C")
      (libsource (lib "eagle-import") (part "L-USL2012C"))
    )
    (comp (ref "L2")
      (value "WE-CBF_0603")
      (footprint "eagle-import:0603")
      (libsource (lib "eagle-import") (part "WE-CBF_0603"))
    )
    (comp (ref "L3")
      (value "WE-CBF_0603")
      (footprint "eagle-import:0603")
      (libsource (lib "eagle-import") (part "WE-CBF_0603"))
    )
    (comp (ref "L5")
      (value "WE-CBF_0603")
      (footprint "eagle-import:0603")
      (libsource (lib "eagle-import") (part "WE-CBF_0603"))
    )
    (comp (ref "R37")
      (value "2.2k")
      (footprint "eagle-import:R0603")
      (libsource (lib "eagle-import") (part "R-US_R0603"))
    )
  )
  (nets
    (net (code "1") (name "+3V3") (class "Default")
      (node (ref "C10") (pin "1") (pinfunction "1_1") (pintype "passive"))
      (node (ref "C16") (pin "+") (pinfunction "+_+") (pintype "passive"))
      (node (ref "C17") (pin "1") (pinfunction "1_1") (pintype "passive"))
      (node (ref "C25") (pin "1") (pinfunction "1_1") (pintype "passive"))
      (node (ref "C26") (pin "1") (pinfunction "1_1") (pintype "passive"))
      (node (ref "C3") (pin "+") (pinfunction "+_+") (pintype "passive"))
      (node (ref "C6") (pin "1") (pinfunction "1_1") (pintype "passive"))
      (node (ref "C9") (pin "1") (pinfunction "1_1") (pintype "passive"))
      (node (ref "D3") (pin "2") (pinfunction "C_2") (pintype "passive"))
      (node (ref "IC1") (pin "3") (pinfunction "VO_3") (pintype "passive"))
      (node (ref "IC4") (pin "1") (pinfunction "VBAT_1") (pintype "power_in"))
      (node (ref "IC4") (pin "17") (pinfunction "VDD_2_17") (pintype "power_in"))
      (node (ref "IC4") (pin "48") (pinfunction "VDD_1_48") (pintype "power_in"))
      (node (ref "IC5") (pin "11") (pinfunction "FLT_11") (pintype "input"))
      (node (ref "IC5") (pin "17") (pinfunction "XSMT_17") (pintype "input"))
      (node (ref "IC5") (pin "20") (pinfunction "DVDD_20") (pintype "power_in"))
      (node (ref "L4") (pin "2") (pinfunction "2_2") (pintype "passive"))
      (node (ref "LED1") (pin "A") (pinfunction "A_A") (pintype "bidirectional"))
      (node (ref "LED2") (pin "A") (pinfunction "A_A") (pintype "bidirectional"))
      (node (ref "LED3") (pin "A") (pinfunction "A_A") (pintype "bidirectional"))
      (node (ref "LED4") (pin "A") (pinfunction "A_A") (pintype "bidirectional"))
      (node (ref "LED5") (pin "A") (pinfunction "A_A") (pintype "bidirectional"))
      (node (ref "LED6") (pin "A") (pinfunction "A_A") (pintype "bidirectional"))
      (node (ref "LED7") (pin "A") (pinfunction "A_A") (pintype "bidirectional"))
      (node (ref "LED8") (pin "A") (pinfunction "A_A") (pintype "bidirectional"))
      (node (ref "R4") (pin "1") (pinfunction "1_1") (pintype "passive"))
    )
    (net (code "2") (name "+3V3_A") (class "Default")
      (node (ref "C19") (pin "1") (pinfunction "1_1") (pintype "passive"))
      (node (ref "C20") (pin "1") (pinfunction "1_1") (pintype "passive"))
      (node (ref "C22") (pin "+") (pinfunction "+_+") (pintype "passive"))
      (node (ref "C23") (pin "1") (pinfunction "1_1") (pintype "passive"))
      (node (ref "C24") (pin "1") (pinfunction "1_1") (pintype "passive"))
      (node (ref "C27") (pin "1") (pinfunction "1_1") (pintype "passive"))
      (node (ref "C28") (pin "1") (pinfunction "1_1") (pintype "passive"))
      (node (ref "C30") (pin "+") (pinfunction "+_+") (pintype "passive"))
      (node (ref "C36") (pin "1") (pinfunction "1_1") (pintype "passive"))
      (node (ref "C44") (pin "1") (pinfunction "1_1") (pintype "passive"))
      (node (ref "IC3") (pin "1") (pinfunction "VO_1") (pintype "passive"))
      (node (ref "IC4") (pin "24") (pinfunction "VDDSD_24") (pintype "power_in"))
      (node (ref "IC4") (pin "25") (pinfunction "VREFSD+_25") (pintype "power_in"))
      (node (ref "IC4") (pin "9") (pinfunction "VDDA_9") (pintype "power_in"))
      (node (ref "IC5") (pin "1") (pinfunction "CPVDD_1") (pintype "bidirectional"))
      (node (ref "IC5") (pin "8") (pinfunction "AVDD_8") (pintype "power_in"))
      (node (ref "IC6") (pin "4") (pinfunction "V+_4") (pintype "power_in"))
      (node (ref "IC7") (pin "4") (pinfunction "V+_4") (pintype "power_in"))
      (node (ref "R1") (pin "P$1") (pinfunction "E_P$1") (pintype "passive"))
      (node (ref "R2") (pin "P$1") (pinfunction "E_P$1") (pintype "passive"))
      (node (ref "R42") (pin "P$1") (pinfunction "E_P$1") (pintype "passive"))
      (node (ref "R43") (pin "P$1") (pinfunction "E_P$1") (pintype "passive"))
      (node (ref "R44") (pin "P$1") (pinfunction "E_P$1") (pintype "passive"))
      (node (ref "R7") (pin "P$1") (pinfunction "E_P$1") (pintype "passive"))
      (node (ref "R8") (pin "P$1") (pinfunction "E_P$1") (pintype "passive"))
    )
    (net (code "3") (name "ADC_FM") (class "Default")
      (node (ref "C40") (pin "2") (pinfunction "2_2") (pintype "passive"))
      (node (ref "IC4") (pin "22") (pinfunction "PE9/SDADC1_AIN7P/SDADC1_AIN8M/SDADC2_AIN7P/SDADC2_AIN8M_22") (pintype "bidirectional"))
      (node (ref "IC7") (pin "1") (pinfunction "OUT_1") (pintype "output"))
      (node (ref "R19") (pin "1") (pinfunction "1_1") (pintype "passive"))
    )
    (net (code "4") (name "ADC_GATE") (class "Default")
      (node (ref "C39") (pin "2") (pinfunction "2_2") (pintype "passive"))
      (node (ref "IC4") (pin "21") (pinfunction "PE8/SDADC1_AIN8P/SDADC2_AIN8P_21") (pintype "bidirectional"))
      (node (ref "IC6") (pin "14") (pinfunction "OUT_14") (pintype "output"))
      (node (ref "R18") (pin "1") (pinfunction "1_1") (pintype "passive"))
    )
    (net (code "5") (name "ADC_HARMONICS") (class "Default")
      (node (ref "C41") (pin "2") (pinfunction "2_2") (pintype "passive"))
      (node (ref "IC4") (pin "28") (pinfunction "PD8/SPI2_SCK/I2S2_CK/USART3_TX/SDADC3_AIN6P_28") (pintype "bidirectional"))
      (node (ref "IC7") (pin "14") (pinfunction "OUT_14") (pintype "output"))
      (node (ref "R20") (pin "1") (pinfunction "1_1") (pintype "passive"))
    )
    (net (code "6") (name "ADC_MODEL") (class "Default")
      (node (ref "C46") (pin "2") (pinfunction "2_2") (pintype "passive"))
      (node (ref "IC4") (pin "19") (pinfunction "PB1/TIM3_CH4/ADC_IN9/SDADC1_AIN5P/SDADC1_AIN6M_19") (pintype "bidirectional"))
      (node (ref "IC6") (pin "7") (pinfunction "OUT_7") (pintype "output"))
      (node (ref "R31") (pin "1") (pinfunction "1_1") (pintype "passive"))
    )
    (net (code "7") (name "ADC_MORPH") (class "Default")
      (node (ref "C49") (pin "2") (pinfunction "2_2") (pintype "passive"))
      (node (ref "IC4") (pin "27") (pinfunction "PB15/SPI2_MOSI/I2S2_SD/SDADC3_AIN7P/SDADC3_AIN8M_27") (pintype "bidirectional"))
      (node (ref "IC7") (pin "8") (pinfunction "OUT_8") (pintype "output"))
      (node (ref "R35") (pin "1") (pinfunction "1_1") (pintype "passive"))
    )
    (net (code "8") (name "ADC_TIMBRE") (class "Default")
      (node (ref "C47") (pin "2") (pinfunction "2_2") (pintype "passive"))
      (node (ref "IC4") (pin "20") (pinfunction "PB2/SDADC1_AIN4P/SDADC2_AIN6P_20") (pintype "bidirectional"))
      (node (ref "IC6") (pin "8") (pinfunction "OUT_8") (pintype "output"))
      (node (ref "R32") (pin "1") (pinfunction "1_1") (pintype "passive"))
    )
    (net (code "9") (name "ADC_TRIG") (class "Default")
      (node (ref "C38") (pin "2") (pinfunction "2_2") (pintype "passive"))
      (node (ref "IC4") (pin "18") (pinfunction "PB0/SPI1_MOSI/I2S1_SD/TIM3_CH3/ADC_IN8/SDADC1_AIN6P_18") (pintype "bidirectional"))
      (node (ref "IC6") (pin "1") (pinfunction "OUT_1") (pintype "output"))
      (node (ref "R17") (pin "1") (pinfunction "1_1") (pintype "passive"))
    )
    (net (code "10") (name "ADC_V_OCT") (class "Default")
      (node (ref "C48") (pin "2") (pinfunction "2_2") (pintype "passive"))
      (node (ref "IC4") (pin "26") (pinfunction "PB14/SPI2_MISO/I2S2_MCK/USART3_RTS/SDADC3_AIN8P_26") (pintype "bidirectional"))
      (node (ref "IC7") (pin "7") (pinfunction "OUT_7") (pintype "output"))
      (node (ref "R34") (pin "1") (pinfunction "1_1") (pintype "passive"))
    )
    (net (code "11") (name "AREF_-10") (class "Default")
      (node (ref "C50") (pin "1") (pinfunction "1_1") (pintype "passive"))
      (node (ref "IC9") (pin "2") (pinfunction "A_2") (pintype "passive"))
      (node (ref "R23") (pin "2") (pinfunction "2_2") (pintype "passive"))
      (node (ref "R25") (pin "2") (pinfunction "2_2") (pintype "passive"))
      (node (ref "R26") (pin "2") (pinfunction "2_2") (pintype "passive"))
      (node (ref "R27") (pin "2") (pinfunction "2_2") (pintype "passive"))
      (node (ref "R29") (pin "2") (pinfunction "2_2") (pintype "passive"))
      (node (ref "R30") (pin "2") (pinfunction "2_2") (pintype "passive"))
      (node (ref "R33") (pin "2") (pinfunction "2_2") (pintype "passive"))
      (node (ref "R36") (pin "2") (pinfunction "2_2") (pintype "passive"))
      (node (ref "R37") (pin "2") (pinfunction "2_2") (pintype "passive"))
    )
    (net (code "12") (name "DAC_BCK") (class "Default")
      (node (ref "IC4") (pin "29") (pinfunction "PA8/SPI2_SCK/I2S2_CK/I2C2_SMBA/USART1_CK/TIM5_CH1_29") (pintype "bidirectional"))
      (node (ref "IC5") (pin "13") (pinfunction "BCK_13") (pintype "input"))
    )
    (net (code "13") (name "DAC_DIN") (class "Default")
      (node (ref "IC4") (pin "31") (pinfunction "PA10/SPI2_MOSI/I2S2_SD/I2C2_SDA/USART1_RX/TIM2_CH4_31") (pintype "bidirectional"))
      (node (ref "IC5") (pin "14") (pinfunction "DIN_14") (pintype "input"))
    )
    (net (code "14") (name "DAC_LRCK") (class "Default")
      (node (ref "IC4") (pin "32") (pinfunction "PA11/SPI2_NSS/I2S2_WS/SPI1_NSS/I2S1_WS/USART1_CTS/CAN_RX/TIM4_CH1/TIM5_CH2_32") (pintype "bidirectional"))
      (node (ref "IC5") (pin "15") (pinfunction "LRCK_15") (pintype "input"))
    )
    (net (code "15") (name "FREQ_ATT") (class "Default")
      (node (ref "C51") (pin "1") (pinfunction "1_1") (pintype "passive"))
      (node (ref "IC4") (pin "15") (pinfunction "PA5/SPI1_SCK/I2S1_CK/TIM2_CH1/ADC_IN5/DAC1_OUT2_15") (pintype "bidirectional"))
      (node (ref "R43") (pin "P$2") (pinfunction "S_P$2") (pintype "passive"))
    )
    (net (code "16") (name "FREQ_POT") (class "Default")
      (node (ref "C11") (pin "1") (pinfunction "1_1") (pintype "passive"))
      (node (ref "IC4") (pin "10") (pinfunction "PA0/USART2_CTS/TIM2_CH1/TIM5_CH1/ADC_IN0_10") (pintype "bidirectional"))
      (node (ref "R1") (pin "P$2") (pinfunction "S_P$2") (pintype "passive"))
    )
    (net (code "17") (name "GND") (class "Default")
      (node (ref "C1") (pin "2") (pinfunction "2_2") (pintype "passive"))
      (node (ref "C10") (pin "2") (pinfunction "2_2") (pintype "passive"))
      (node (ref "C11") (pin "2") (pinfunction "2_2") (pintype "passive"))
      (node (ref "C12") (pin "2") (pinfunction "2_2") (pintype "passive"))
      (node (ref "C13") (pin "2") (pinfunction "2_2") (pintype "passive"))
      (node (ref "C14") (pin "1") (pinfunction "1_1") (pintype "passive"))
      (node (ref "C15") (pin "2") (pinfunction "2_2") (pintype "passive"))
      (node (ref "C16") (pin "-") (pinfunction "-_-") (pintype "passive"))
      (node (ref "C17") (pin "2") (pinfunction "2_2") (pintype "passive"))
      (node (ref "C18") (pin "2") (pinfunction "2_2") (pintype "passive"))
      (node (ref "C19") (pin "2") (pinfunction "2_2") (pintype "passive"))
      (node (ref "C2") (pin "2") (pinfunction "2_2") (pintype "passive"))
      (node (ref "C20") (pin "2") (pinfunction "2_2") (pintype "passive"))
      (node (ref "C21") (pin "1") (pinfunction "1_1") (pintype "passive"))
      (node (ref "C22") (pin "-") (pinfunction "-_-") (pintype "passive"))
      (node (ref "C23") (pin "2") (pinfunction "2_2") (pintype "passive"))
      (node (ref "C24") (pin "2") (pinfunction "2_2") (pintype "passive"))
      (node (ref "C25") (pin "2") (pinfunction "2_2") (pintype "passive"))
      (node (ref "C26") (pin "2") (pinfunction "2_2") (pintype "passive"))
      (node (ref "C27") (pin "2") (pinfunction "2_2") (pintype "passive"))
      (node (ref "C28") (pin "2") (pinfunction "2_2") (pintype "passive"))
      (node (ref "C3") (pin "-") (pinfunction "-_-") (pintype "passive"))
      (node (ref "C30") (pin "-") (pinfunction "-_-") (pintype "passive"))
      (node (ref "C31") (pin "2") (pinfunction "2_2") (pintype "passive"))
      (node (ref "C32") (pin "2") (pinfunction "2_2") (pintype "passive"))
      (node (ref "C33") (pin "2") (pinfunction "2_2") (pintype "passive"))
      (node (ref "C34") (pin "2") (pinfunction "2_2") (pintype "passive"))
      (node (ref "C35") (pin "2") (pinfunction "2_2") (pintype "passive"))
      (node (ref "C36") (pin "2") (pinfunction "2_2") (pintype "passive"))
      (node (ref "C37") (pin "2") (pinfunction "2_2") (pintype "passive"))
      (node (ref "C4") (pin "-") (pinfunction "-_-") (pintype "passive"))
      (node (ref "C44") (pin "2") (pinfunction "2_2") (pintype "passive"))
      (node (ref "C45") (pin "1") (pinfunction "1_1") (pintype "passive"))
      (node (ref "C5") (pin "+") (pinfunction "+_+") (pintype "passive"))
      (node (ref "C50") (pin "2") (pinfunction "2_2") (pintype "passive"))
      (node (ref "C51") (pin "2") (pinfunction "2_2") (pintype "passive"))
      (node (ref "C52") (pin "2") (pinfunction "2_2") (pintype "passive"))
      (node (ref "C53") (pin "2") (pinfunction "2_2") (pintype "passive"))
      (node (ref "C54") (pin "2") (pinfunction "2_2") (pintype "passive"))
      (node (ref "C55") (pin "2") (pinfunction "2_2") (pintype "passive"))
      (node (ref "C56") (pin "2") (pinfunction "2_2") (pintype "passive"))
      (node (ref "C57") (pin "2") (pinfunction "2_2") (pintype "passive"))
      (node (ref "C58") (pin "2") (pinfunction "2_2") (pintype "passive"))
      (node (ref "C59") (pin "2") (pinfunction "2_2") (pintype "passive"))
      (node (ref "C6") (pin "2") (pinfunction "2_2") (pintype "passive"))
      (node (ref "C60") (pin "2") (pinfunction "2_2") (pintype "passive"))
      (node (ref "C61") (pin "2") (pinfunction "2_2") (pintype "passive"))
      (node (ref "C7") (pin "-") (pinfunction "-_-") (pintype "passive"))
      (node (ref "C8") (pin "2") (pinfunction "2_2") (pintype "passive"))
      (node (ref "C9") (pin "2") (pinfunction "2_2") (pintype "passive"))
      (node (ref "D3") (pin "1") (pinfunction "A_1") (pintype "passive"))
      (node (ref "IC1") (pin "2") (pinfunction "GND_2") (pintype "passive"))
      (node (ref "IC2") (pin "1") (pinfunction "GND_1") (pintype "bidirectional"))
      (node (ref "IC2") (pin "21") (pinfunction "BLANK_21") (pintype "bidirectional"))
      (node (ref "IC3") (pin "2") (pinfunction "GND_2") (pintype "passive"))
      (node (ref "IC4") (pin "23") (pinfunction "VSSSD/VREFSD-_23") (pintype "power_in"))
      (node (ref "IC4") (pin "44") (pinfunction "BOOT0_44") (pintype "bidirectional"))
      (node (ref "IC4") (pin "47") (pinfunction "VSS_1_47") (pintype "power_in"))
      (node (ref "IC4") (pin "8") (pinfunction "VSSA_8") (pintype "power_in"))
      (node (ref "IC5") (pin "10") (pinfunction "DEMP_10") (pintype "input"))
      (node (ref "IC5") (pin "12") (pinfunction "SCK_12") (pintype "input"))
      (node (ref "IC5") (pin "16") (pinfunction "FMT_16") (pintype "input"))
      (node (ref "IC5") (pin "19") (pinfunction "DGND_19") (pintype "power_in"))
      (node (ref "IC5") (pin "3") (pinfunction "CPGND_3") (pintype "bidirectional"))
      (node (ref "IC5") (pin "9") (pinfunction "AGND_9") (pintype "power_in"))
      (node (ref "IC6") (pin "10") (pinfunction "+IN_10") (pintype "input"))
      (node (ref "IC6") (pin "11") (pinfunction "V-_11") (pintype "power_in"))
      (node (ref "IC6") (pin "12") (pinfunction "+IN_12") (pintype "input"))
      (node (ref "IC6") (pin "3") (pinfunction "+IN_3") (pintype "input"))
      (node (ref "IC6") (pin "5") (pinfunction "+IN_5") (pintype "input"))
      (node (ref "IC7") (pin "10") (pinfunction "+IN_10") (pintype "input"))
      (node (ref "IC7") (pin "11") (pinfunction "V-_11") (pintype "power_in"))
      (node (ref "IC7") (pin "12") (pinfunction "+IN_12") (pintype "input"))
      (node (ref "IC7") (pin "3") (pinfunction "+IN_3") (pintype "input"))
      (node (ref "IC7") (pin "5") (pinfunction "+IN_5") (pintype "input"))
      (node (ref "IC8") (pin "3") (pinfunction "+IN_3") (pintype "input"))
      (node (ref "IC8") (pin "5") (pinfunction "+IN_5") (pintype "input"))
      (node (ref "IC9") (pin "1") (pinfunction "C_1") (pintype "passive"))
      (node (ref "J1") (pin "P1") (pinfunction "1_P1") (pintype "passive"))
      (node (ref "J1") (pin "P2") (pinfunction "2_P2") (pintype "passive"))
      (node (ref "J10") (pin "P1") (pinfunction "1_P1") (pintype "passive"))
      (node (ref "J2") (pin "P1") (pinfunction "1_P1") (pintype "passive"))
      (node (ref "J3") (pin "P1") (pinfunction "1_P1") (pintype "passive"))
      (node (ref "J4") (pin "P1") (pinfunction "1_P1") (pintype "passive"))
      (node (ref "J5") (pin "P1") (pinfunction "1_P1") (pintype "passive"))
      (node (ref "J5") (pin "P2") (pinfunction "2_P2") (pintype "passive"))
      (node (ref "J6") (pin "P1") (pinfunction "1_P1") (pintype "passive"))
      (node (ref "J7") (pin "P1") (pinfunction "1_P1") (pintype "passive"))
      (node (ref "J8") (pin "P1") (pinfunction "1_P1") (pintype "passive"))
      (node (ref "J8") (pin "P2") (pinfunction "2_P2") (pintype "passive"))
      (node (ref "J9") (pin "P1") (pinfunction "1_P1") (pintype "passive"))
      (node (ref "JP6") (pin "1") (pinfunction "1_1") (pintype "passive"))
      (node (ref "JP8") (pin "3") (pinfunction "3_3") (pintype "passive"))
      (node (ref "JP8") (pin "4") (pinfunction "4_4") (pintype "passive"))
      (node (ref "JP8") (pin "5") (pinfunction "5_5") (pintype "passive"))
      (node (ref "JP8") (pin "6") (pinfunction "6_6") (pintype "passive"))
      (node (ref "JP8") (pin "7") (pinfunction "7_7") (pintype "passive"))
      (node (ref "JP8") (pin "8") (pinfunction "8_8") (pintype "passive"))
      (node (ref "Q1") (pin "2") (pinfunction "LID1_2") (pintype "power_in"))
      (node (ref "Q1") (pin "4") (pinfunction "LID2_4") (pintype "power_in"))
      (node (ref "R1") (pin "P$3") (pinfunction "A_P$3") (pintype "passive"))
      (node (ref "R2") (pin "P$3") (pinfunction "A_P$3") (pintype "passive"))
      (node (ref "R3") (pin "2") (pinfunction "2_2") (pintype "passive"))
      (node (ref "R42") (pin "P$3") (pinfunction "A_P$3") (pintype "passive"))
      (node (ref "R43") (pin "P$3") (pinfunction "A_P$3") (pintype "passive"))
      (node (ref "R44") (pin "P$3") (pinfunction "A_P$3") (pintype "passive"))
      (node (ref "R7") (pin "P$3") (pinfunction "A_P$3") (pintype "passive"))
      (node (ref "R8") (pin "P$3") (pinfunction "A_P$3") (pintype "passive"))
      (node (ref "SW1") (pin "1") (pinfunction "1_1") (pintype "passive"))
      (node (ref "SW1") (pin "2") (pinfunction "2_2") (pintype "passive"))
      (node (ref "SW2") (pin "1") (pinfunction "1_1") (pintype "passive"))
      (node (ref "SW2") (pin "2") (pinfunction "2_2") (pintype "passive"))
    )
    (net (code "18") (name "HARMONICS_POT") (class "Default")
      (node (ref "C12") (pin "1") (pinfunction "1_1") (pintype "passive"))
      (node (ref "IC4") (pin "12") (pinfunction "PA2/SPI3_MISO/I2S3_MCK/USART2_TX/TIM2_CH3/TIM5_CH3/ADC_IN2_12") (pintype "bidirectional"))
      (node (ref "R2") (pin "P$2") (pinfunction "S_P$2") (pintype "passive"))
    )
    (net (code "19") (name "LEDS_SCK") (class "Default")
      (node (ref "IC2") (pin "3") (pinfunction "SCLK_3") (pintype "bidirectional"))
      (node (ref "IC4") (pin "33") (pinfunction "PA12/SPI1_SCK/I2S1_CK/USART1_RTS/CAN_TX/TIM4_CH2/TIM5_CH3_33") (pintype "bidirectional"))
    )
    (net (code "20") (name "LEDS_SIN") (class "Default")
      (node (ref "IC2") (pin "2") (pinfunction "SIN_2") (pintype "bidirectional"))
      (node (ref "IC4") (pin "35") (pinfunction "PF6/SPI1_MOSI/I2S1_SD/USART3_RTS/TIM4_CH4/I2C2_SCL_35") (pintype "bidirectional"))
    )
    (net (code "21") (name "LEDS_SS") (class "Default")
      (node (ref "IC2") (pin "4") (pinfunction "LAT_4") (pintype "bidirectional"))
      (node (ref "IC4") (pin "36") (pinfunction "PF7/I2C2_SDA/USART2_CK_36") (pintype "bidirectional"))
    )
    (net (code "22") (name "MORPH_ATT") (class "Default")
      (node (ref "C52") (pin "1") (pinfunction "1_1") (pintype "passive"))
      (node (ref "IC4") (pin "14") (pinfunction "PA4/SPI1_NSS/I2S1_WS/SPI3_NSS/I2S3_WS/USART2_CK/TIM3_CH2/ADC_IN4/DAC1_OUT1_14") (pintype "bidirectional"))
      (node (ref "R44") (pin "P$2") (pinfunction "S_P$2") (pintype "passive"))
    )
    (net (code "23") (name "MORPH_POT") (class "Default")
      (node (ref "C34") (pin "1") (pinfunction "1_1") (pintype "passive"))
      (node (ref "IC4") (pin "11") (pinfunction "PA1/SPI3_SCK/I2S3_CK/USART2_RTS/TIM2_CH2/TIM5_CH2/ADC_IN1_11") (pintype "bidirectional"))
      (node (ref "R8") (pin "P$2") (pinfunction "S_P$2") (pintype "passive"))
    )
    (net (code "24") (name "NORMALIZATION_PROBE") (class "Default")
      (node (ref "D3") (pin "3") (pinfunction "AC_3") (pintype "passive"))
      (node (ref "IC4") (pin "30") (pinfunction "PA9/SPI_MISO/I2S2_MCK/I2C2_SCL/USART1_TX/TIM2_CH3_30") (pintype "bidirectional"))
      (node (ref "R45") (pin "2") (pinfunction "2_2") (pintype "passive"))
      (node (ref "R48") (pin "2") (pinfunction "2_2") (pintype "passive"))
      (node (ref "R49") (pin "2") (pinfunction "2_2") (pintype "passive"))
      (node (ref "R50") (pin "1") (pinfunction "1_1") (pintype "passive"))
      (node (ref "R51") (pin "2") (pinfunction "2_2") (pintype "passive"))
    )
    (net (code "25") (name "Net-(C2-Pad1)") (class "Default")
      (node (ref "C2") (pin "1") (pinfunction "1_1") (pintype "passive"))
      (node (ref "D1") (pin "C") (pinfunction "C_C") (pintype "passive"))
      (node (ref "L1") (pin "1") (pinfunction "1_1") (pintype "passive"))
      (node (ref "L2") (pin "2") (pinfunction "2_2") (pintype "passive"))
      (node (ref "L5") (pin "2") (pinfunction "2_2") (pintype "passive"))
    )
    (net (code "26") (name "Net-(C21-Pad2)") (class "Default")
      (node (ref "C21") (pin "2") (pinfunction "2_2") (pintype "passive"))
      (node (ref "Q1") (pin "1") (pinfunction "1_1") (pintype "passive"))
      (node (ref "R6") (pin "2") (pinfunction "2_2") (pintype "passive"))
    )
    (net (code "27") (name "Net-(C33-Pad1)") (class "Default")
      (node (ref "C33") (pin "1") (pinfunction "1_1") (pintype "passive"))
      (node (ref "R11") (pin "1") (pinfunction "1_1") (pintype "passive"))
      (node (ref "R21") (pin "2") (pinfunction "2_2") (pintype "passive"))
    )
    (net (code "28") (name "Net-(C35-Pad1)") (class "Default")
      (node (ref "C35") (pin "1") (pinfunction "1_1") (pintype "passive"))
      (node (ref "R12") (pin "1") (pinfunction "1_1") (pintype "passive"))
      (node (ref "R16") (pin "2") (pinfunction "2_2") (pintype "passive"))
    )
    (net (code "29") (name "Net-(D1-PadA)") (class "Default")
      (node (ref "D1") (pin "A") (pinfunction "A_A") (pintype "passive"))
      (node (ref "JP8") (pin "10") (pinfunction "10_10") (pintype "passive"))
      (node (ref "JP8") (pin "9") (pinfunction "9_9") (pintype "passive"))
    )
    (net (code "30") (name "Net-(D2-PadA)") (class "Default")
      (node (ref "D2") (pin "A") (pinfunction "A_A") (pintype "passive"))
      (node (ref "L3") (pin "2") (pinfunction "2_2") (pintype "passive"))
    )
    (net (code "31") (name "Net-(D2-PadC)") (class "Default")
      (node (ref "D2") (pin "C") (pinfunction "C_C") (pintype "passive"))
      (node (ref "JP8") (pin "1") (pinfunction "1_1") (pintype "passive"))
      (node (ref "JP8") (pin "2") (pinfunction "2_2") (pintype "passive"))
    )
    (net (code "32") (name "Net-(IC1-VI)") (class "Default")
      (node (ref "C1") (pin "1") (pinfunction "1_1") (pintype "passive"))
      (node (ref "IC1") (pin "1") (pinfunction "VI_1") (pintype "input"))
      (node (ref "L1") (pin "2") (pinfunction "2_2") (pintype "passive"))
    )
    (net (code "33") (name "Net-(IC2-IREF)") (class "Default")
      (node (ref "IC2") (pin "23") (pinfunction "IREF_23") (pintype "bidirectional"))
      (node (ref "R3") (pin "1") (pinfunction "1_1") (pintype "passive"))
    )
    (net (code "34") (name "Net-(IC2-OUT0)") (class "Default")
      (node (ref "IC2") (pin "5") (pinfunction "OUT0_5") (pintype "bidirectional"))
      (node (ref "LED5") (pin "RED_C") (pinfunction "RED_RED_C") (pintype "bidirectional"))
    )
    (net (code "35") (name "Net-(IC2-OUT1)") (class "Default")
      (node (ref "IC2") (pin "6") (pinfunction "OUT1_6") (pintype "bidirectional"))
      (node (ref "LED5") (pin "GREEN_C") (pinfunction "GRN_GREEN_C") (pintype "bidirectional"))
    )
    (net (code "36") (name "Net-(IC2-OUT2)") (class "Default")
      (node (ref "IC2") (pin "7") (pinfunction "OUT2_7") (pintype "bidirectional"))
      (node (ref "LED6") (pin "RED_C") (pinfunction "RED_RED_C") (pintype "bidirectional"))
    )
    (net (code "37") (name "Net-(IC2-OUT3)") (class "Default")
      (node (ref "IC2") (pin "8") (pinfunction "OUT3_8") (pintype "bidirectional"))
      (node (ref "LED6") (pin "GREEN_C") (pinfunction "GRN_GREEN_C") (pintype "bidirectional"))
    )
    (net (code "38") (name "Net-(IC2-OUT4)") (class "Default")
      (node (ref "IC2") (pin "9") (pinfunction "OUT4_9") (pintype "bidirectional"))
      (node (ref "LED7") (pin "RED_C") (pinfunction "RED_RED_C") (pintype "bidirectional"))
    )
    (net (code "39") (name "Net-(IC2-OUT5)") (class "Default")
      (node (ref "IC2") (pin "10") (pinfunction "OUT5_10") (pintype "bidirectional"))
      (node (ref "LED7") (pin "GREEN_C") (pinfunction "GRN_GREEN_C") (pintype "bidirectional"))
    )
    (net (code "40") (name "Net-(IC2-OUT6)") (class "Default")
      (node (ref "IC2") (pin "11") (pinfunction "OUT6_11") (pintype "bidirectional"))
      (node (ref "LED8") (pin "RED_C") (pinfunction "RED_RED_C") (pintype "bidirectional"))
    )
    (net (code "41") (name "Net-(IC2-OUT7)") (class "Default")
      (node (ref "IC2") (pin "12") (pinfunction "OUT7_12") (pintype "bidirectional"))
      (node (ref "LED8") (pin "GREEN_C") (pinfunction "GRN_GREEN_C") (pintype "bidirectional"))
    )
    (net (code "42") (name "Net-(IC2-OUT8)") (class "Default")
      (node (ref "IC2") (pin "13") (pinfunction "OUT8_13") (pintype "bidirectional"))
      (node (ref "LED4") (pin "RED_C") (pinfunction "RED_RED_C") (pintype "bidirectional"))
    )
    (net (code "43") (name "Net-(IC2-OUT9)") (class "Default")
      (node (ref "IC2") (pin "14") (pinfunction "OUT9_14") (pintype "bidirectional"))
      (node (ref "LED4") (pin "GREEN_C") (pinfunction "GRN_GREEN_C") (pintype "bidirectional"))
    )
    (net (code "44") (name "Net-(IC2-OUT10)") (class "Default")
      (node (ref "IC2") (pin "15") (pinfunction "OUT10_15") (pintype "bidirectional"))
      (node (ref "LED3") (pin "RED_C") (pinfunction "RED_RED_C") (pintype "bidirectional"))
    )
    (net (code "45") (name "Net-(IC2-OUT11)") (class "Default")
      (node (ref "IC2") (pin "16") (pinfunction "OUT11_16") (pintype "bidirectional"))
      (node (ref "LED3") (pin "GREEN_C") (pinfunction "GRN_GREEN_C") (pintype "bidirectional"))
    )
    (net (code "46") (name "Net-(IC2-OUT12)") (class "Default")
      (node (ref "IC2") (pin "17") (pinfunction "OUT12_17") (pintype "bidirectional"))
      (node (ref "LED2") (pin "RED_C") (pinfunction "RED_RED_C") (pintype "bidirectional"))
    )
    (net (code "47") (name "Net-(IC2-OUT13)") (class "Default")
      (node (ref "IC2") (pin "18") (pinfunction "OUT13_18") (pintype "bidirectional"))
      (node (ref "LED2") (pin "GREEN_C") (pinfunction "GRN_GREEN_C") (pintype "bidirectional"))
    )
    (net (code "48") (name "Net-(IC2-OUT14)") (class "Default")
      (node (ref "IC2") (pin "19") (pinfunction "OUT14_19") (pintype "bidirectional"))
      (node (ref "LED1") (pin "RED_C") (pinfunction "RED_RED_C") (pintype "bidirectional"))
    )
    (net (code "49") (name "Net-(IC2-OUT15)") (class "Default")
      (node (ref "IC2") (pin "20") (pinfunction "OUT15_20") (pintype "bidirectional"))
      (node (ref "LED1") (pin "GREEN_C") (pinfunction "GRN_GREEN_C") (pintype "bidirectional"))
    )
    (net (code "50") (name "Net-(IC2-VCC)") (class "Default")
      (node (ref "C7") (pin "+") (pinfunction "+_+") (pintype "passive"))
      (node (ref "C8") (pin "1") (pinfunction "1_1") (pintype "passive"))
      (node (ref "IC2") (pin "24") (pinfunction "VCC_24") (pintype "bidirectional"))
      (node (ref "L4") (pin "1") (pinfunction "1_1") (pintype "passive"))
    )
    (net (code "51") (name "Net-(IC3-VI)") (class "Default")
      (node (ref "C13") (pin "1") (pinfunction "1_1") (pintype "passive"))
      (node (ref "IC3") (pin "3") (pinfunction "VI_3") (pintype "input"))
      (node (ref "L5") (pin "1") (pinfunction "1_1") (pintype "passive"))
    )
    (net (code "52") (name "Net-(IC4-PF0{slash}OSC_IN{slash}I2C2_SDA)") (class "Default")
      (node (ref "IC4") (pin "5") (pinfunction "PF0/OSC_IN/I2C2_SDA_5") (pintype "bidirectional"))
      (node (ref "R5") (pin "1") (pinfunction "1_1") (pintype "passive"))
    )
    (net (code "53") (name "Net-(IC4-PF1{slash}OSC_OUT{slash}I2C2_SCL)") (class "Default")
      (node (ref "IC4") (pin "6") (pinfunction "PF1/OSC_OUT/I2C2_SCL_6") (pintype "bidirectional"))
      (node (ref "R6") (pin "1") (pinfunction "1_1") (pintype "passive"))
    )
    (net (code "54") (name "Net-(IC5-CAPM)") (class "Default")
      (node (ref "C29") (pin "2") (pinfunction "2_2") (pintype "passive"))
      (node (ref "IC5") (pin "4") (pinfunction "CAPM_4") (pintype "bidirectional"))
    )
    (net (code "55") (name "Net-(IC5-CAPP)") (class "Default")
      (node (ref "C29") (pin "1") (pinfunction "1_1") (pintype "passive"))
      (node (ref "IC5") (pin "2") (pinfunction "CAPP_2") (pintype "bidirectional"))
    )
    (net (code "56") (name "Net-(IC5-LDOO)") (class "Default")
      (node (ref "C18") (pin "1") (pinfunction "1_1") (pintype "passive"))
      (node (ref "IC5") (pin "18") (pinfunction "LDOO_18") (pintype "bidirectional"))
    )
    (net (code "57") (name "Net-(IC5-OUTL)") (class "Default")
      (node (ref "IC5") (pin "6") (pinfunction "OUTL_6") (pintype "output"))
      (node (ref "R11") (pin "2") (pinfunction "2_2") (pintype "passive"))
    )
    (net (code "58") (name "Net-(IC5-OUTR)") (class "Default")
      (node (ref "IC5") (pin "7") (pinfunction "OUTR_7") (pintype "output"))
      (node (ref "R12") (pin "2") (pinfunction "2_2") (pintype "passive"))
    )
    (net (code "59") (name "Net-(IC5-VNEG)") (class "Default")
      (node (ref "C31") (pin "1") (pinfunction "1_1") (pintype "passive"))
      (node (ref "IC5") (pin "5") (pinfunction "VNEG_5") (pintype "input"))
    )
    (net (code "60") (name "Net-(IC6A--IN)") (class "Default")
      (node (ref "C38") (pin "1") (pinfunction "1_1") (pintype "passive"))
      (node (ref "IC6") (pin "2") (pinfunction "-IN_2") (pintype "input"))
      (node (ref "R17") (pin "2") (pinfunction "2_2") (pintype "passive"))
      (node (ref "R24") (pin "1") (pinfunction "1_1") (pintype "passive"))
      (node (ref "R25") (pin "1") (pinfunction "1_1") (pintype "passive"))
    )
    (net (code "61") (name "Net-(IC6B--IN)") (class "Default")
      (node (ref "C46") (pin "1") (pinfunction "1_1") (pintype "passive"))
      (node (ref "IC6") (pin "6") (pinfunction "-IN_6") (pintype "input"))
      (node (ref "R30") (pin "1") (pinfunction "1_1") (pintype "passive"))
      (node (ref "R31") (pin "2") (pinfunction "2_2") (pintype "passive"))
      (node (ref "R40") (pin "1") (pinfunction "1_1") (pintype "passive"))
    )
    (net (code "62") (name "Net-(IC6C--IN)") (class "Default")
      (node (ref "C47") (pin "1") (pinfunction "1_1") (pintype "passive"))
      (node (ref "IC6") (pin "9") (pinfunction "-IN_9") (pintype "input"))
      (node (ref "R32") (pin "2") (pinfunction "2_2") (pintype "passive"))
      (node (ref "R33") (pin "1") (pinfunction "1_1") (pintype "passive"))
      (node (ref "R41") (pin "1") (pinfunction "1_1") (pintype "passive"))
    )
    (net (code "63") (name "Net-(IC6D--IN)") (class "Default")
      (node (ref "C39") (pin "1") (pinfunction "1_1") (pintype "passive"))
      (node (ref "IC6") (pin "13") (pinfunction "-IN_13") (pintype "input"))
      (node (ref "R14") (pin "1") (pinfunction "1_1") (pintype "passive"))
      (node (ref "R18") (pin "2") (pinfunction "2_2") (pintype "passive"))
      (node (ref "R26") (pin "1") (pinfunction "1_1") (pintype "passive"))
    )
    (net (code "64") (name "Net-(IC7A--IN)") (class "Default")
      (node (ref "C40") (pin "1") (pinfunction "1_1") (pintype "passive"))
      (node (ref "IC7") (pin "2") (pinfunction "-IN_2") (pintype "input"))
      (node (ref "R15") (pin "1") (pinfunction "1_1") (pintype "passive"))
      (node (ref "R19") (pin "2") (pinfunction "2_2") (pintype "passive"))
      (node (ref "R23") (pin "1") (pinfunction "1_1") (pintype "passive"))
    )
    (net (code "65") (name "Net-(IC7B--IN)") (class "Default")
      (node (ref "C48") (pin "1") (pinfunction "1_1") (pintype "passive"))
      (node (ref "IC7") (pin "6") (pinfunction "-IN_6") (pintype "input"))
      (node (ref "R29") (pin "1") (pinfunction "1_1") (pintype "passive"))
      (node (ref "R34") (pin "2") (pinfunction "2_2") (pintype "passive"))
      (node (ref "R38") (pin "1") (pinfunction "1_1") (pintype "passive"))
    )
    (net (code "66") (name "Net-(IC7C--IN)") (class "Default")
      (node (ref "C49") (pin "1") (pinfunction "1_1") (pintype "passive"))
      (node (ref "IC7") (pin "9") (pinfunction "-IN_9") (pintype "input"))
      (node (ref "R35") (pin "2") (pinfunction "2_2") (pintype "passive"))
      (node (ref "R36") (pin "1") (pinfunction "1_1") (pintype "passive"))
      (node (ref "R39") (pin "1") (pinfunction "1_1") (pintype "passive"))
    )
    (net (code "67") (name "Net-(IC7D--IN)") (class "Default")
      (node (ref "C41") (pin "1") (pinfunction "1_1") (pintype "passive"))
      (node (ref "IC7") (pin "13") (pinfunction "-IN_13") (pintype "input"))
      (node (ref "R13") (pin "1") (pinfunction "1_1") (pintype "passive"))
      (node (ref "R20") (pin "2") (pinfunction "2_2") (pintype "passive"))
      (node (ref "R27") (pin "1") (pinfunction "1_1") (pintype "passive"))
    )
    (net (code "68") (name "Net-(IC8A--IN)") (class "Default")
      (node (ref "C42") (pin "1") (pinfunction "1_1") (pintype "passive"))
      (node (ref "IC8") (pin "2") (pinfunction "-IN_2") (pintype "input"))
      (node (ref "R21") (pin "1") (pinfunction "1_1") (pintype "passive"))
      (node (ref "R22") (pin "2") (pinfunction "2_2") (pintype "passive"))
    )
    (net (code "69") (name "Net-(IC8A-OUT)") (class "Default")
      (node (ref "C42") (pin "2") (pinfunction "2_2") (pintype "passive"))
      (node (ref "IC8") (pin "1") (pinfunction "OUT_1") (pintype "output"))
      (node (ref "R22") (pin "1") (pinfunction "1_1") (pintype "passive"))
      (node (ref "R46") (pin "2") (pinfunction "2_2") (pintype "passive"))
    )
    (net (code "70") (name "Net-(IC8B--IN)") (class "Default")
      (node (ref "C43") (pin "1") (pinfunction "1_1") (pintype "passive"))
      (node (ref "IC8") (pin "6") (pinfunction "-IN_6") (pintype "input"))
      (node (ref "R16") (pin "1") (pinfunction "1_1") (pintype "passive"))
      (node (ref "R28") (pin "2") (pinfunction "2_2") (pintype "passive"))
    )
    (net (code "71") (name "Net-(IC8B-OUT)") (class "Default")
      (node (ref "C43") (pin "2") (pinfunction "2_2") (pintype "passive"))
      (node (ref "IC8") (pin "7") (pinfunction "OUT_7") (pintype "output"))
      (node (ref "R28") (pin "1") (pinfunction "1_1") (pintype "passive"))
      (node (ref "R47") (pin "2") (pinfunction "2_2") (pintype "passive"))
    )
    (net (code "72") (name "Net-(J1-3)") (class "Default")
      (node (ref "C55") (pin "1") (pinfunction "1_1") (pintype "passive"))
      (node (ref "J1") (pin "P3") (pinfunction "3_P3") (pintype "passive"))
      (node (ref "R40") (pin "2") (pinfunction "2_2") (pintype "passive"))
    )
    (net (code "73") (name "Net-(J2-2)") (class "Default")
      (node (ref "J2") (pin "P2") (pinfunction "2_P2") (pintype "passive"))
      (node (ref "R48") (pin "1") (pinfunction "1_1") (pintype "passive"))
    )
    (net (code "74") (name "Net-(J2-3)") (class "Default")
      (node (ref "C56") (pin "1") (pinfunction "1_1") (pintype "passive"))
      (node (ref "J2") (pin "P3") (pinfunction "3_P3") (pintype "passive"))
      (node (ref "R41") (pin "2") (pinfunction "2_2") (pintype "passive"))
    )
    (net (code "75") (name "Net-(J3-2)") (class "Default")
      (node (ref "J3") (pin "P2") (pinfunction "2_P2") (pintype "passive"))
      (node (ref "R49") (pin "1") (pinfunction "1_1") (pintype "passive"))
    )
    (net (code "76") (name "Net-(J3-3)") (class "Default")
      (node (ref "C57") (pin "1") (pinfunction "1_1") (pintype "passive"))
      (node (ref "J3") (pin "P3") (pinfunction "3_P3") (pintype "passive"))
      (node (ref "R15") (pin "2") (pinfunction "2_2") (pintype "passive"))
    )
    (net (code "77") (name "Net-(J4-2)") (class "Default")
      (node (ref "J4") (pin "P2") (pinfunction "2_P2") (pintype "passive"))
      (node (ref "R45") (pin "1") (pinfunction "1_1") (pintype "passive"))
    )
    (net (code "78") (name "Net-(J4-3)") (class "Default")
      (node (ref "C54") (pin "1") (pinfunction "1_1") (pintype "passive"))
      (node (ref "J4") (pin "P3") (pinfunction "3_P3") (pintype "passive"))
      (node (ref "R39") (pin "2") (pinfunction "2_2") (pintype "passive"))
    )
    (net (code "79") (name "Net-(J5-3)") (class "Default")
      (node (ref "C58") (pin "1") (pinfunction "1_1") (pintype "passive"))
      (node (ref "J5") (pin "P3") (pinfunction "3_P3") (pintype "passive"))
      (node (ref "R13") (pin "2") (pinfunction "2_2") (pintype "passive"))
    )
    (net (code "80") (name "Net-(J6-2)") (class "Default")
      (node (ref "J6") (pin "P2") (pinfunction "2_P2") (pintype "passive"))
      (node (ref "R50") (pin "2") (pinfunction "2_2") (pintype "passive"))
    )
    (net (code "81") (name "Net-(J6-3)") (class "Default")
      (node (ref "C59") (pin "1") (pinfunction "1_1") (pintype "passive"))
      (node (ref "J6") (pin "P3") (pinfunction "3_P3") (pintype "passive"))
      (node (ref "R24") (pin "2") (pinfunction "2_2") (pintype "passive"))
    )
    (net (code "82") (name "Net-(J7-2)") (class "Default")
      (node (ref "J7") (pin "P2") (pinfunction "2_P2") (pintype "passive"))
      (node (ref "R51") (pin "1") (pinfunction "1_1") (pintype "passive"))
    )
    (net (code "83") (name "Net-(J7-3)") (class "Default")
      (node (ref "C61") (pin "1") (pinfunction "1_1") (pintype "passive"))
      (node (ref "J7") (pin "P3") (pinfunction "3_P3") (pintype "passive"))
      (node (ref "R14") (pin "2") (pinfunction "2_2") (pintype "passive"))
    )
    (net (code "84") (name "Net-(J8-3)") (class "Default")
      (node (ref "C60") (pin "1") (pinfunction "1_1") (pintype "passive"))
      (node (ref "J8") (pin "P3") (pinfunction "3_P3") (pintype "passive"))
      (node (ref "R38") (pin "2") (pinfunction "2_2") (pintype "passive"))
    )
    (net (code "85") (name "Net-(J9-3)") (class "Default")
      (node (ref "J9") (pin "P3") (pinfunction "3_P3") (pintype "passive"))
      (node (ref "R46") (pin "1") (pinfunction "1_1") (pintype "passive"))
    )
    (net (code "86") (name "Net-(J10-3)") (class "Default")
      (node (ref "J10") (pin "P3") (pinfunction "3_P3") (pintype "passive"))
      (node (ref "R47") (pin "1") (pinfunction "1_1") (pintype "passive"))
    )
    (net (code "87") (name "Net-(JP5-Pad1)") (class "Default")
      (node (ref "JP5") (pin "1") (pinfunction "1_1") (pintype "passive"))
      (node (ref "R9") (pin "1") (pinfunction "1_1") (pintype "passive"))
    )
    (net (code "88") (name "Net-(JP5-Pad2)") (class "Default")
      (node (ref "JP5") (pin "2") (pinfunction "2_2") (pintype "passive"))
      (node (ref "R10") (pin "1") (pinfunction "1_1") (pintype "passive"))
    )
    (net (code "89") (name "Net-(Q1B-2)") (class "Default")
      (node (ref "C14") (pin "2") (pinfunction "2_2") (pintype "passive"))
      (node (ref "Q1") (pin "3") (pinfunction "2_3") (pintype "passive"))
      (node (ref "R5") (pin "2") (pinfunction "2_2") (pintype "passive"))
    )
    (net (code "90") (name "RESET") (class "Default")
      (node (ref "C15") (pin "1") (pinfunction "1_1") (pintype "passive"))
      (node (ref "IC4") (pin "7") (pinfunction "NRST_7") (pintype "bidirectional"))
      (node (ref "JP6") (pin "4") (pinfunction "4_4") (pintype "passive"))
      (node (ref "R4") (pin "2") (pinfunction "2_2") (pintype "passive"))
    )
    (net (code "91") (name "RX") (class "Default")
      (node (ref "IC4") (pin "46") (pinfunction "PB9/SPI2_NSS/I2S2_WS/I2C1_SDA/USART3_RX/CAN_TX/TIM4_CH4_46") (pintype "bidirectional"))
      (node (ref "R9") (pin "2") (pinfunction "2_2") (pintype "passive"))
    )
    (net (code "92") (name "SWCLK") (class "Default")
      (node (ref "IC4") (pin "37") (pinfunction "PA14/I2C1_SDA/JTCK-SWCLK_37") (pintype "bidirectional"))
      (node (ref "JP6") (pin "3") (pinfunction "3_3") (pintype "passive"))
    )
    (net (code "93") (name "SWDIO") (class "Default")
      (node (ref "IC4") (pin "34") (pinfunction "PA13/SPI1_MISO/I2S1_MCK/USART3_CTS/TIM4_CH3/TIM5_CH4/JTMS-SWDIO_34") (pintype "bidirectional"))
      (node (ref "JP6") (pin "2") (pinfunction "2_2") (pintype "passive"))
    )
    (net (code "94") (name "SW_1") (class "Default")
      (node (ref "IC4") (pin "43") (pinfunction "PB7/I2C1_SDA/USART1_RX/TIM4_CH2_43") (pintype "bidirectional"))
      (node (ref "SW1") (pin "3") (pinfunction "3_3") (pintype "passive"))
      (node (ref "SW1") (pin "4") (pinfunction "4_4") (pintype "passive"))
    )
    (net (code "95") (name "SW_2") (class "Default")
      (node (ref "IC4") (pin "42") (pinfunction "PB6/I2C1_SCL/USART1_TX/TIM4_CH1_42") (pintype "bidirectional"))
      (node (ref "SW2") (pin "3") (pinfunction "3_3") (pintype "passive"))
      (node (ref "SW2") (pin "4") (pinfunction "4_4") (pintype "passive"))
    )
    (net (code "96") (name "TIMBRE_ATT") (class "Default")
      (node (ref "C53") (pin "1") (pinfunction "1_1") (pintype "passive"))
      (node (ref "IC4") (pin "16") (pinfunction "PA6/SPI1_MISO/I2S1_MCK/TIM3_CH1/ADC_IN6/DAC2_OUT1_16") (pintype "bidirectional"))
      (node (ref "R42") (pin "P$2") (pinfunction "S_P$2") (pintype "passive"))
    )
    (net (code "97") (name "TIMBRE_POT") (class "Default")
      (node (ref "C32") (pin "1") (pinfunction "1_1") (pintype "passive"))
      (node (ref "IC4") (pin "13") (pinfunction "PA3/SPI3_MOSI/I2S3_SD/USART2_RX/TIM2_CH4/TIM5_CH4/ADC_IN3_13") (pintype "bidirectional"))
      (node (ref "R7") (pin "P$2") (pinfunction "S_P$2") (pintype "passive"))
    )
    (net (code "98") (name "TX") (class "Default")
      (node (ref "IC4") (pin "45") (pinfunction "PB8/SPI2_SCK/I2S2_CK/I2C1_SCL/USART3_TX/CAN_RX/TIM4_CH3_45") (pintype "bidirectional"))
      (node (ref "R10") (pin "2") (pinfunction "2_2") (pintype "passive"))
    )
    (net (code "99") (name "VCC") (class "Default")
      (node (ref "C37") (pin "1") (pinfunction "1_1") (pintype "passive"))
      (node (ref "C4") (pin "+") (pinfunction "+_+") (pintype "passive"))
      (node (ref "IC8") (pin "8") (pinfunction "V+_8") (pintype "power_in"))
      (node (ref "L2") (pin "1") (pinfunction "1_1") (pintype "passive"))
    )
    (net (code "100") (name "VEE") (class "Default")
      (node (ref "C45") (pin "2") (pinfunction "2_2") (pintype "passive"))
      (node (ref "C5") (pin "-") (pinfunction "-_-") (pintype "passive"))
      (node (ref "IC8") (pin "4") (pinfunction "V-_4") (pintype "power_in"))
      (node (ref "L3") (pin "1") (pinfunction "1_1") (pintype "passive"))
      (node (ref "R37") (pin "1") (pinfunction "1_1") (pintype "passive"))
    )
    (net (code "101") (name "unconnected-(IC2-SOUT-Pad22)") (class "Default")
      (node (ref "IC2") (pin "22") (pinfunction "SOUT_22") (pintype "bidirectional"))
    )
    (net (code "102") (name "unconnected-(IC4-PA15{slash}SPI1_NSS{slash}I2S1_WS{slash}SPI3_NSS{slash}I2S3_WS{slash}I2C1_SCL{slash}TIM2_CH1_ETR{slash}JTDI-Pad38)") (class "Default")
      (node (ref "IC4") (pin "38") (pinfunction "PA15/SPI1_NSS/I2S1_WS/SPI3_NSS/I2S3_WS/I2C1_SCL/TIM2_CH1_ETR/JTDI_38") (pintype "bidirectional"))
    )
    (net (code "103") (name "unconnected-(IC4-PB3{slash}SPI1_SCK{slash}I2S1_CK{slash}SPI3_SCK{slash}I2S3_CK{slash}USART2_TX{slash}TIM2_CH2{slash}JTDO{slash}SPI3_SCK{slash}JTDO-Pad39)") (class "Default")
      (node (ref "IC4") (pin "39") (pinfunction "PB3/SPI1_SCK/I2S1_CK/SPI3_SCK/I2S3_CK/USART2_TX/TIM2_CH2/JTDO/SPI3_SCK/JTDO_39") (pintype "bidirectional"))
    )
    (net (code "104") (name "unconnected-(IC4-PB4{slash}SPI1_MISO{slash}I2S1_MCK{slash}SPI3_MISO{slash}I2S3_MCK{slash}USART2_RX{slash}TIM3_CH1{slash}NJTRST-Pad40)") (class "Default")
      (node (ref "IC4") (pin "40") (pinfunction "PB4/SPI1_MISO/I2S1_MCK/SPI3_MISO/I2S3_MCK/USART2_RX/TIM3_CH1/NJTRST_40") (pintype "bidirectional"))
    )
    (net (code "105") (name "unconnected-(IC4-PB5{slash}SPI1_MOSI{slash}I2S1_SD{slash}SPI3_MOSI{slash}I2S3_SD{slash}I2C1_SMBAI{slash}USART2_CK{slash}TIM3_CH2-Pad41)") (class "Default")
      (node (ref "IC4") (pin "41") (pinfunction "PB5/SPI1_MOSI/I2S1_SD/SPI3_MOSI/I2S3_SD/I2C1_SMBAI/USART2_CK/TIM3_CH2_41") (pintype "bidirectional"))
    )
    (net (code "106") (name "unconnected-(IC4-PC13{slash}TIMESTAMP{slash}RTC_TAMPER1-Pad2)") (class "Default")
      (node (ref "IC4") (pin "2") (pinfunction "PC13/TIMESTAMP/RTC_TAMPER1_2") (pintype "bidirectional"))
    )
    (net (code "107") (name "unconnected-(IC4-PC14{slash}OSC32_IN-Pad3)") (class "Default")
      (node (ref "IC4") (pin "3") (pinfunction "PC14/OSC32_IN_3") (pintype "bidirectional"))
    )
    (net (code "108") (name "unconnected-(IC4-PC15{slash}OSC32_OUT-Pad4)") (class "Default")
      (node (ref "IC4") (pin "4") (pinfunction "PC15/OSC32_OUT_4") (pintype "bidirectional"))
    )
    (net (code "109") (name "unconnected-(J9-2-PadP2)") (class "Default")
      (node (ref "J9") (pin "P2") (pinfunction "2_P2") (pintype "passive"))
    )
    (net (code "110") (name "unconnected-(J10-2-PadP2)") (class "Default")
      (node (ref "J10") (pin "P2") (pinfunction "2_P2") (pintype "passive"))
    )
  )
)
